# Ascii_of_Main_Board_V1_1.net
KiCad netlist of a schematic drawn in Altium Designer
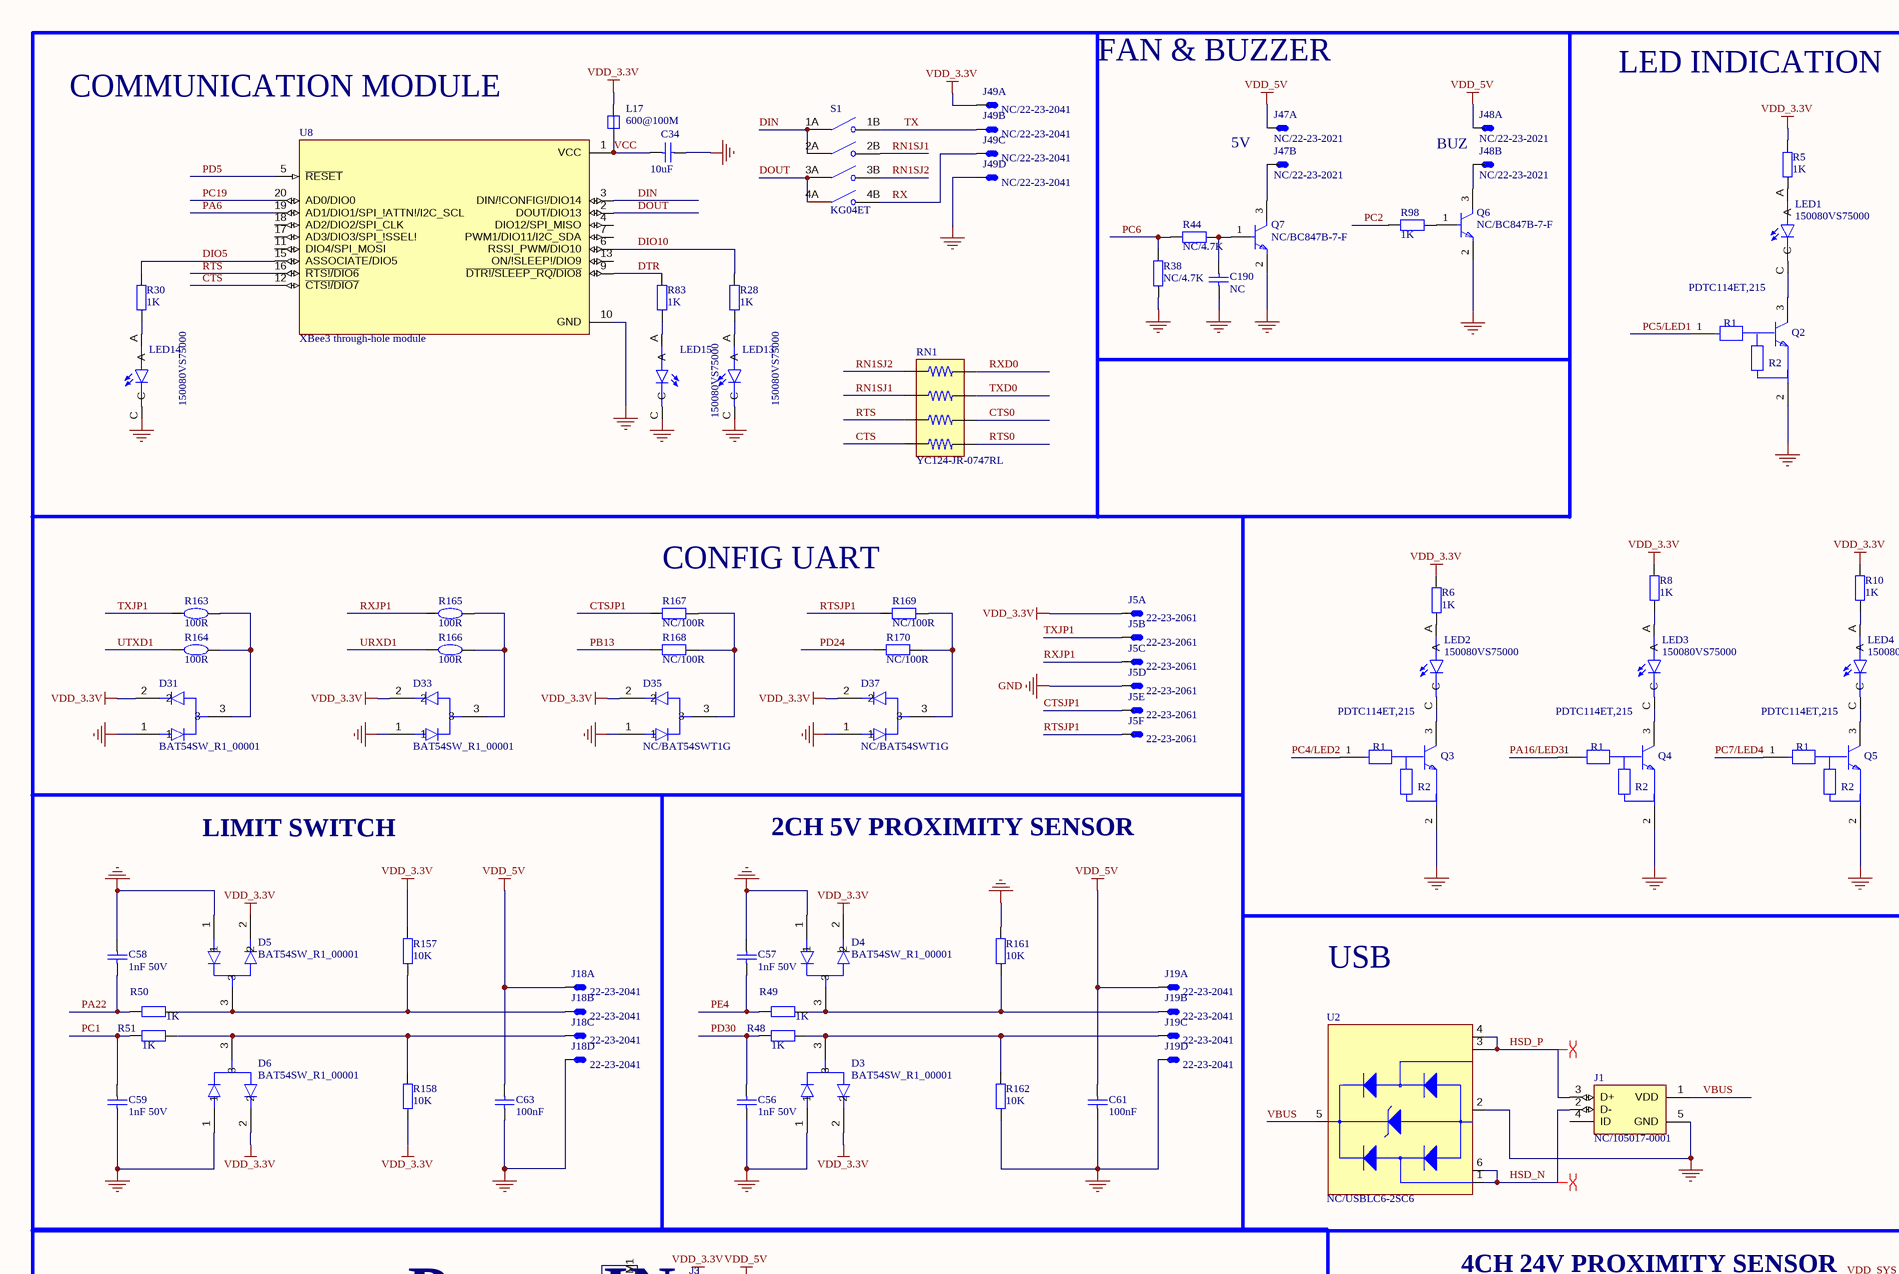
[diagram p0: Ascii of Main Board V1.1.SchDoc, top left]
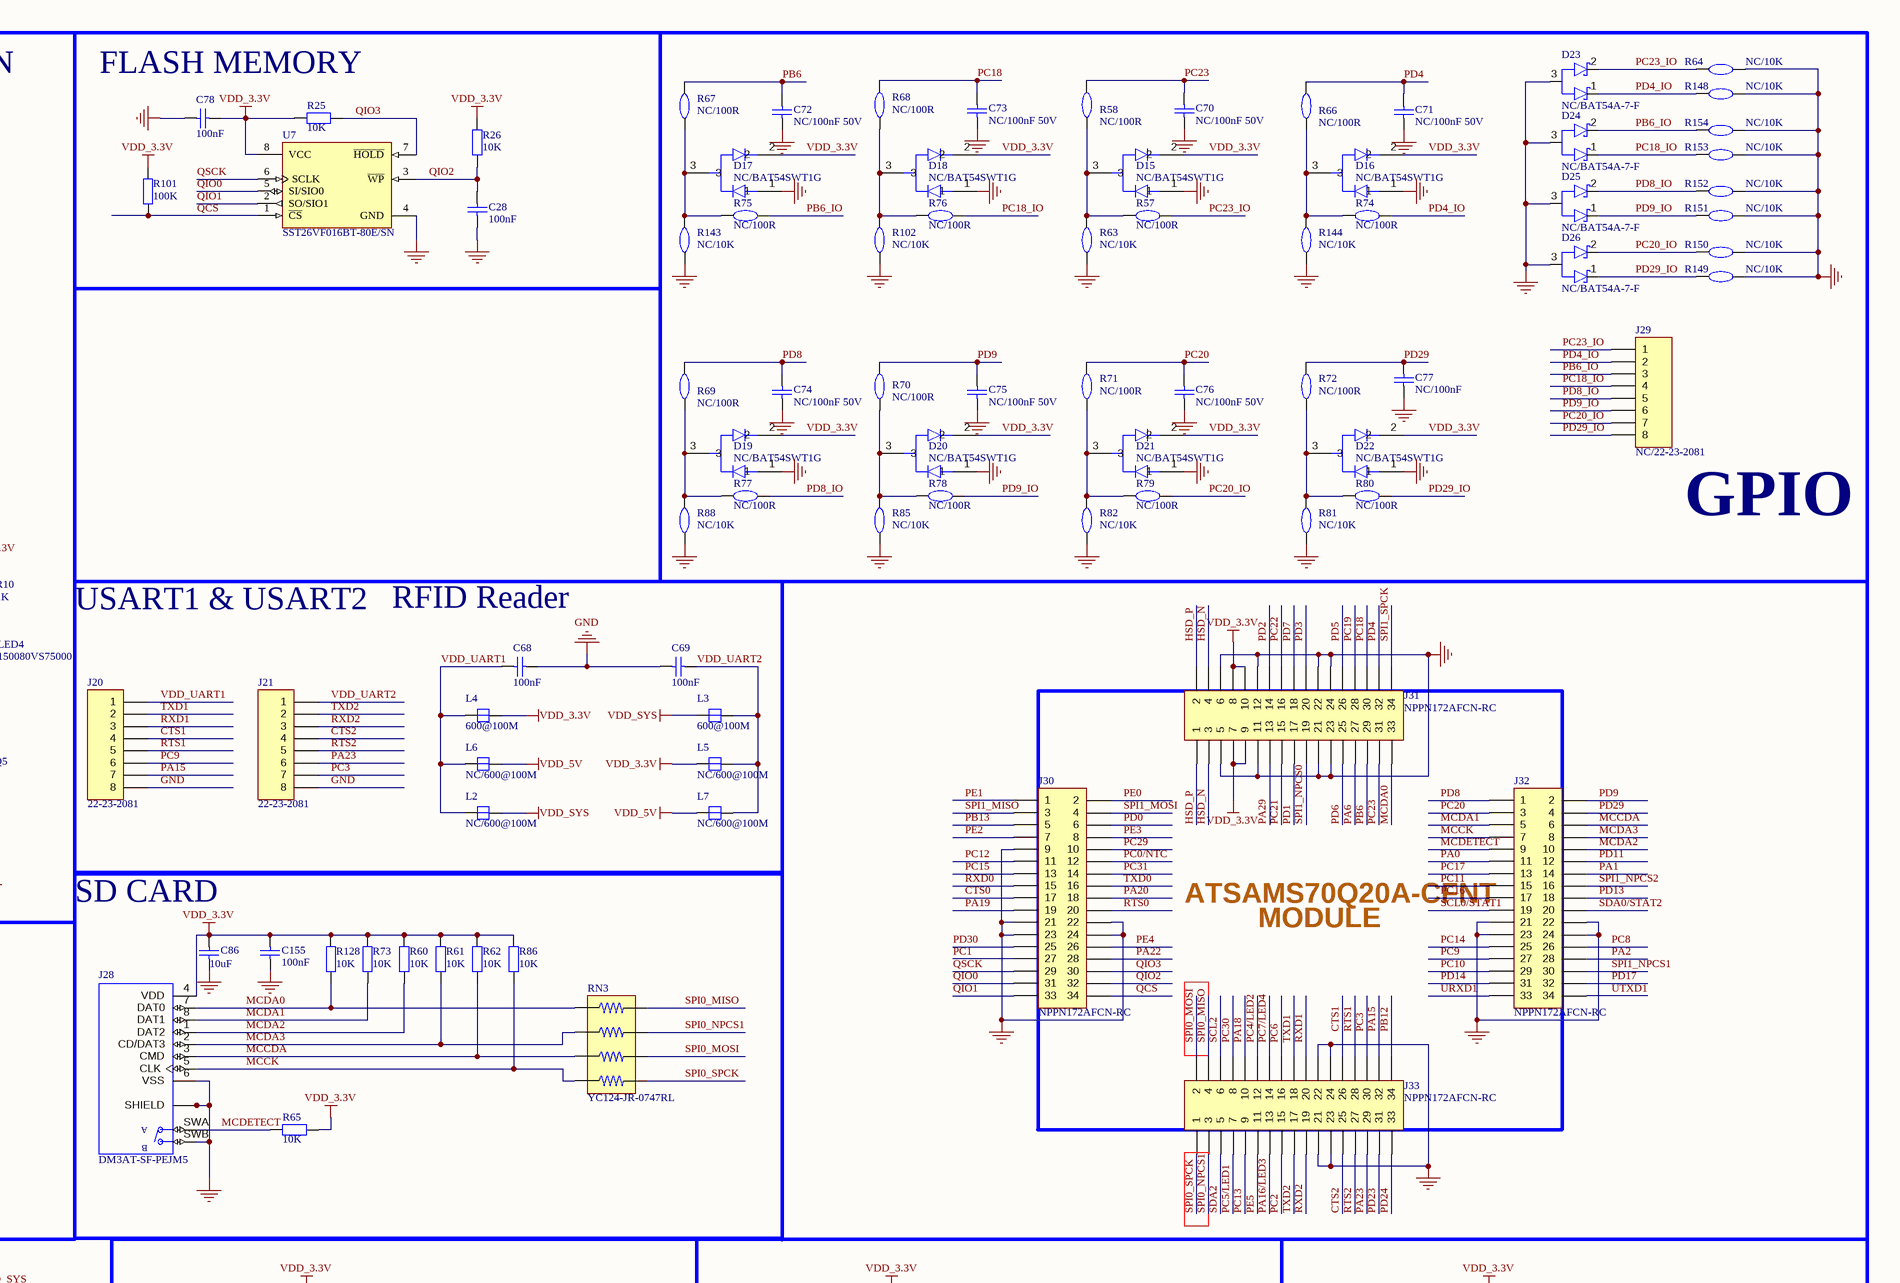
[diagram p1: Ascii of Main Board V1.1.SchDoc, top right]
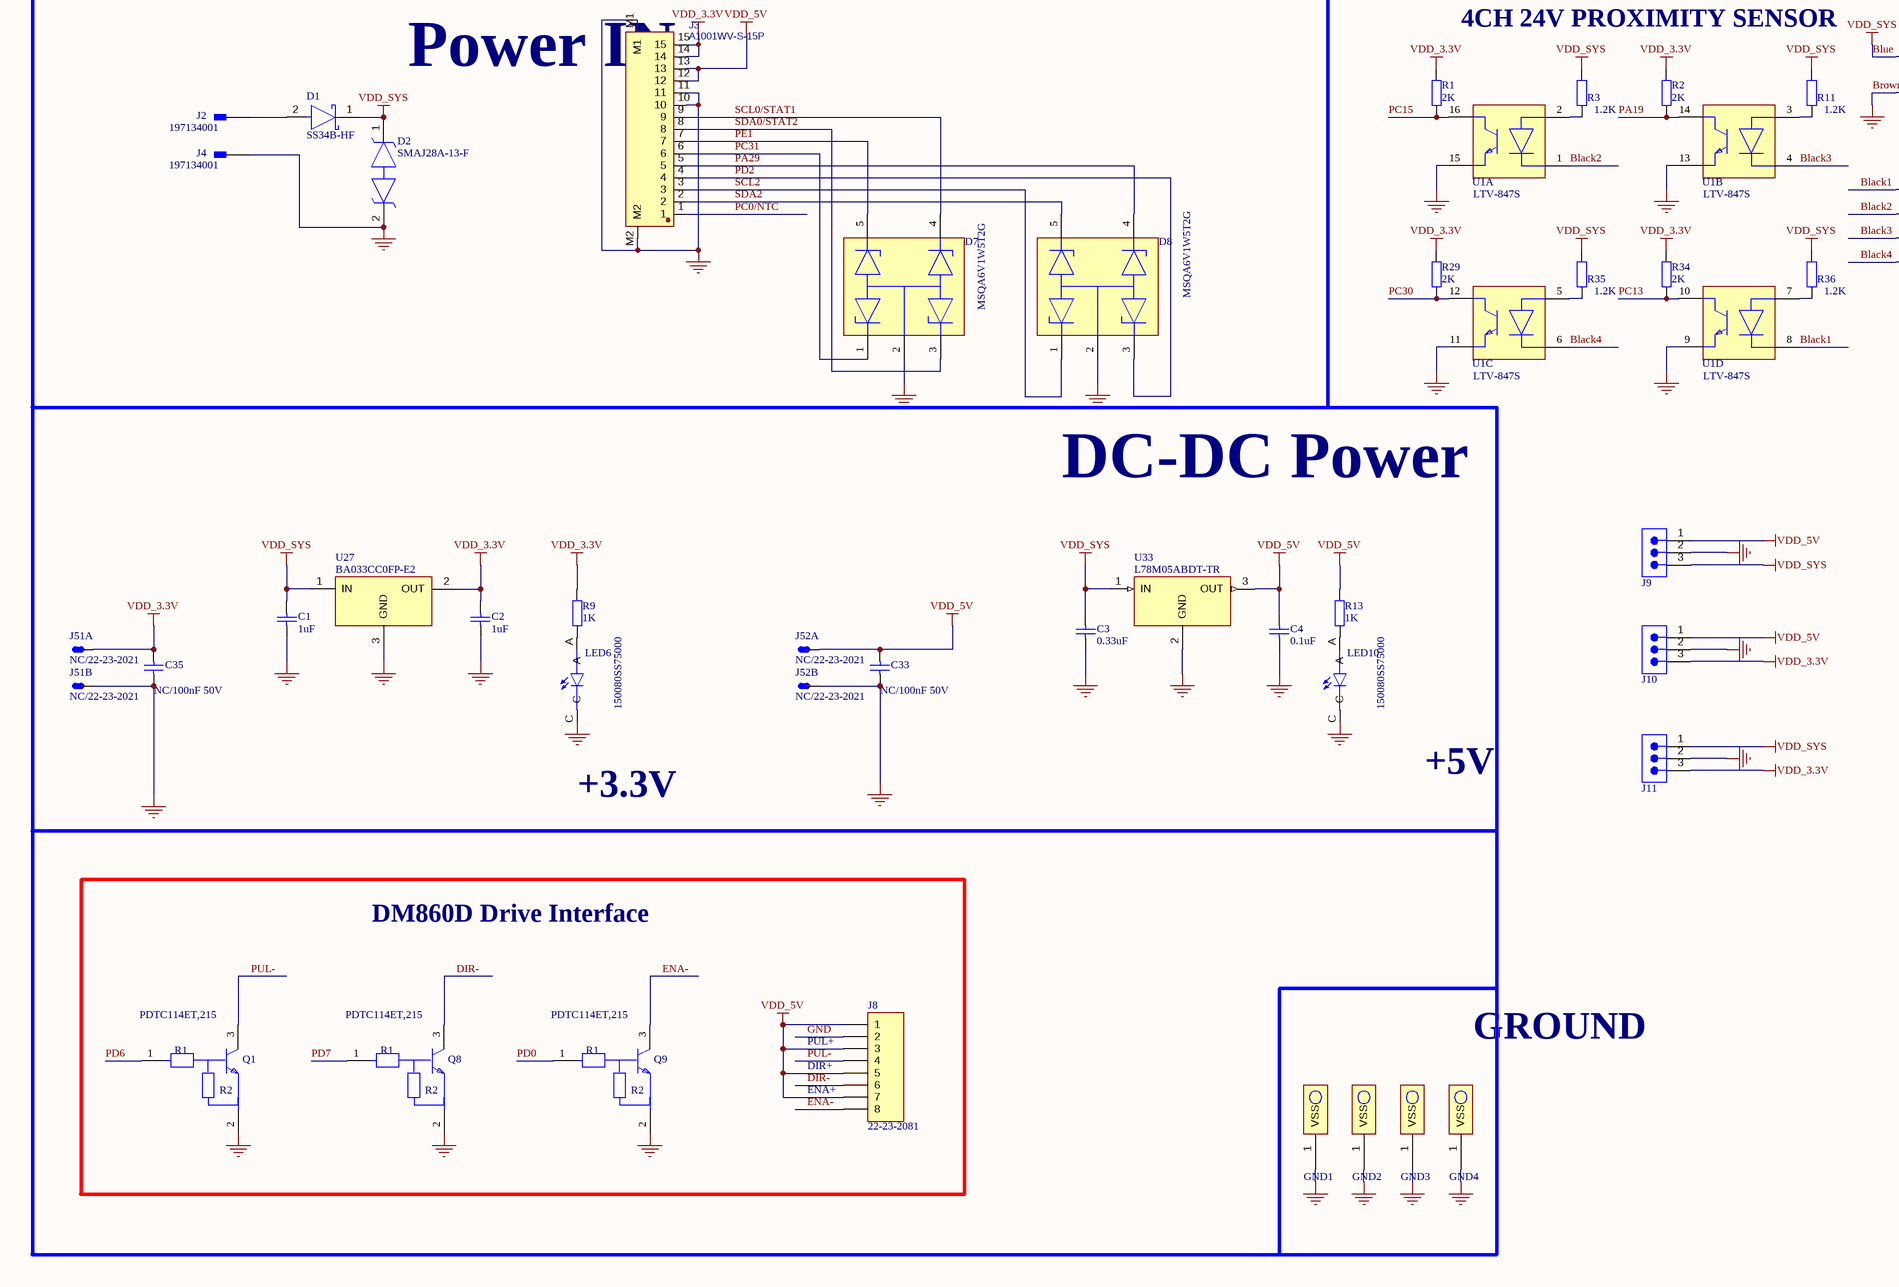
[diagram p2: Ascii of Main Board V1.1.SchDoc, bottom left]
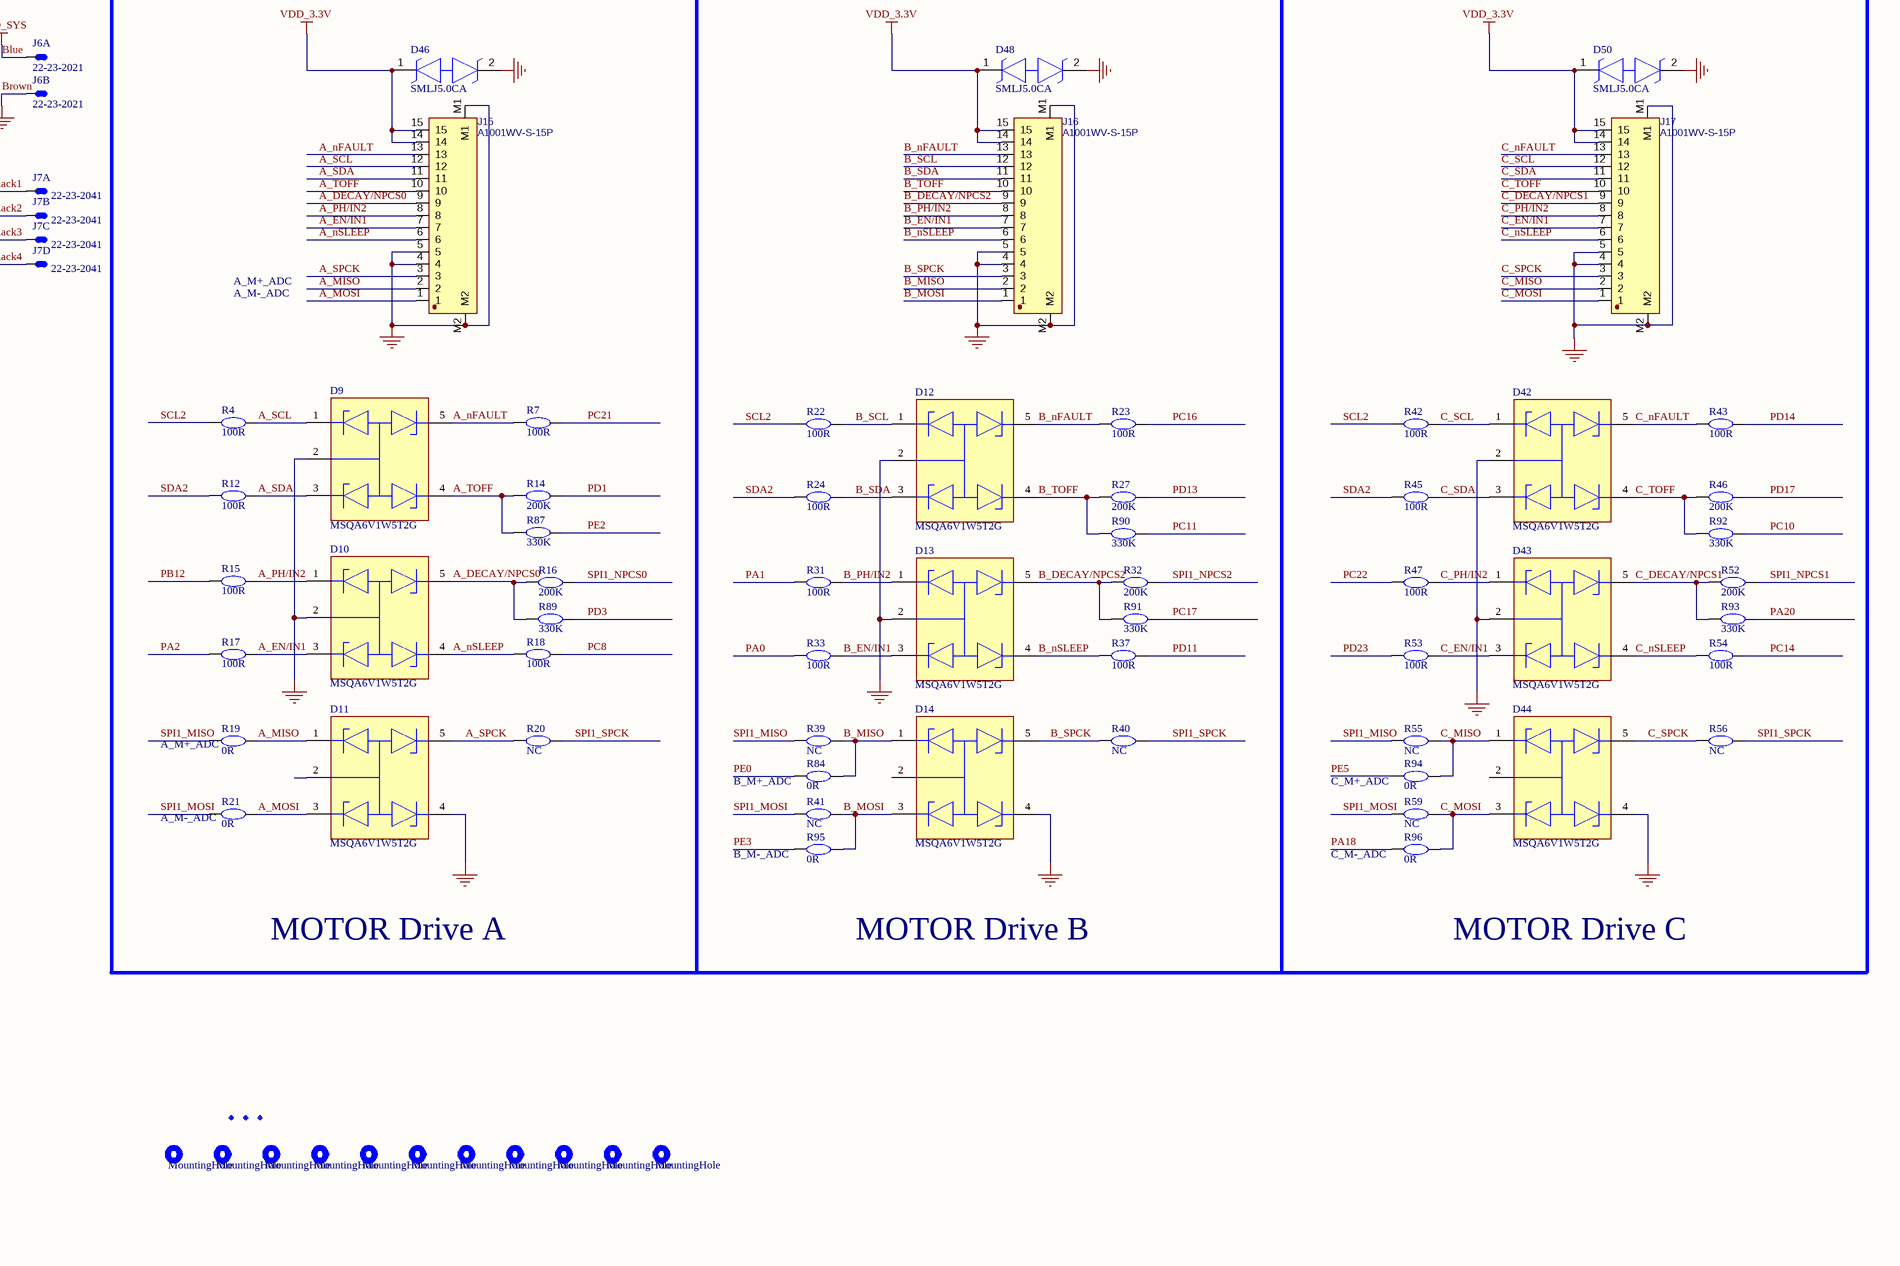
[diagram p3: Ascii of Main Board V1.1.SchDoc, bottom right]

(export (version "E")
  (design (tool "Eeschema 10.0.6"))
  (components
    (comp (ref "C1")
      (value "1uF")
      (footprint "C_0603_1608Metric")
      (description "CAP CER 1UF 50V X7R 0603")
      (fields (field (name "PUBLISHER") "Altium Limited"))
      (libsource (lib "Miscellaneous Devices") (part "Cap Semi"))
    )
    (comp (ref "C2")
      (value "1uF")
      (footprint "C_0603_1608Metric")
      (description "CAP CER 1UF 50V X7R 0603")
      (fields (field (name "PUBLISHER") "Altium Limited"))
      (libsource (lib "Miscellaneous Devices") (part "Cap Semi"))
    )
    (comp (ref "C3")
      (value "0.33uF")
      (footprint "C_0603_1608Metric")
      (description "CAP CER 0.33UF 50V X7R 0603")
      (fields (field (name "PUBLISHER") "Altium Limited"))
      (libsource (lib "Miscellaneous Devices") (part "Cap Semi"))
    )
    (comp (ref "C4")
      (value "0.1uF")
      (footprint "C_0603_1608Metric")
      (description "CAP CER 0.1UF 50V X7R 0603")
      (fields (field (name "PUBLISHER") "Altium Limited"))
      (libsource (lib "Miscellaneous Devices") (part "Cap Semi"))
    )
    (comp (ref "C28")
      (value "100nF")
      (footprint "C_0603_1608Metric")
      (description "CAP CER 0.1UF 50V X7R 0603")
      (fields (field (name "PUBLISHER") "Altium Limited"))
      (libsource (lib "Miscellaneous Devices") (part "Cap Semi"))
    )
    (comp (ref "C33")
      (value "NC/100nF 50V")
      (footprint "C_0603_1608Metric")
      (description "08055C103KAT2A")
      (fields (field (name "PUBLISHER") "Altium Limited"))
      (libsource (lib "Miscellaneous Devices") (part "Cap Semi"))
    )
    (comp (ref "C34")
      (value "10uF")
      (footprint "C_1206_3216Metric")
      (description "CAP CER 10UF 50V X5R 1206")
      (fields (field (name "PUBLISHER") "Altium Limited"))
      (libsource (lib "Miscellaneous Devices") (part "Cap Semi"))
    )
    (comp (ref "C35")
      (value "NC/100nF 50V")
      (footprint "C_0603_1608Metric")
      (description "08055C103KAT2A")
      (fields (field (name "PUBLISHER") "Altium Limited"))
      (libsource (lib "Miscellaneous Devices") (part "Cap Semi"))
    )
    (comp (ref "C56")
      (value "1nF 50V")
      (footprint "C_0603_1608Metric")
      (description "CAP CER 1000PF 50V X7R 0603")
      (fields (field (name "PUBLISHER") "Altium Limited"))
      (libsource (lib "Miscellaneous Devices") (part "Cap Semi"))
    )
    (comp (ref "C57")
      (value "1nF 50V")
      (footprint "C_0603_1608Metric")
      (description "CAP CER 1000PF 50V X7R 0603")
      (fields (field (name "PUBLISHER") "Altium Limited"))
      (libsource (lib "Miscellaneous Devices") (part "Cap Semi"))
    )
    (comp (ref "C58")
      (value "1nF 50V")
      (footprint "C_0603_1608Metric")
      (description "CAP CER 1000PF 50V X7R 0603")
      (fields (field (name "PUBLISHER") "Altium Limited"))
      (libsource (lib "Miscellaneous Devices") (part "Cap Semi"))
    )
    (comp (ref "C59")
      (value "1nF 50V")
      (footprint "C_0603_1608Metric")
      (description "CAP CER 1000PF 50V X7R 0603")
      (fields (field (name "PUBLISHER") "Altium Limited"))
      (libsource (lib "Miscellaneous Devices") (part "Cap Semi"))
    )
    (comp (ref "C61")
      (value "100nF")
      (footprint "C_0603_1608Metric")
      (description "CAP CER 0.1UF 50V X7R 0603")
      (fields (field (name "PUBLISHER") "Altium Limited"))
      (libsource (lib "Miscellaneous Devices") (part "Cap Semi"))
    )
    (comp (ref "C63")
      (value "100nF")
      (footprint "C_0603_1608Metric")
      (description "CAP CER 0.1UF 50V X7R 0603")
      (fields (field (name "PUBLISHER") "Altium Limited"))
      (libsource (lib "Miscellaneous Devices") (part "Cap Semi"))
    )
    (comp (ref "C68")
      (value "100nF")
      (footprint "C_0603_1608Metric")
      (description "CAP CER 0.1UF 50V X7R 0603")
      (fields (field (name "PUBLISHER") "Altium Limited"))
      (libsource (lib "Miscellaneous Devices") (part "Cap Semi"))
    )
    (comp (ref "C69")
      (value "100nF")
      (footprint "C_0603_1608Metric")
      (description "CAP CER 0.1UF 50V X7R 0603")
      (fields (field (name "PUBLISHER") "Altium Limited"))
      (libsource (lib "Miscellaneous Devices") (part "Cap Semi"))
    )
    (comp (ref "C70")
      (value "NC/100nF 50V")
      (footprint "C_0603_1608Metric")
      (description "0805J0500104KXT")
      (fields (field (name "PUBLISHER") "Altium Limited"))
      (libsource (lib "Miscellaneous Devices") (part "Cap Semi"))
    )
    (comp (ref "C71")
      (value "NC/100nF 50V")
      (footprint "C_0603_1608Metric")
      (description "0805J0500104KXT")
      (fields (field (name "PUBLISHER") "Altium Limited"))
      (libsource (lib "Miscellaneous Devices") (part "Cap Semi"))
    )
    (comp (ref "C72")
      (value "NC/100nF 50V")
      (footprint "C_0603_1608Metric")
      (description "0805J0500104KXT")
      (fields (field (name "PUBLISHER") "Altium Limited"))
      (libsource (lib "Miscellaneous Devices") (part "Cap Semi"))
    )
    (comp (ref "C73")
      (value "NC/100nF 50V")
      (footprint "C_0603_1608Metric")
      (description "0805J0500104KXT")
      (fields (field (name "PUBLISHER") "Altium Limited"))
      (libsource (lib "Miscellaneous Devices") (part "Cap Semi"))
    )
    (comp (ref "C74")
      (value "NC/100nF 50V")
      (footprint "C_0603_1608Metric")
      (description "0805J0500104KXT")
      (fields (field (name "PUBLISHER") "Altium Limited"))
      (libsource (lib "Miscellaneous Devices") (part "Cap Semi"))
    )
    (comp (ref "C75")
      (value "NC/100nF 50V")
      (footprint "C_0603_1608Metric")
      (description "0805J0500104KXT")
      (fields (field (name "PUBLISHER") "Altium Limited"))
      (libsource (lib "Miscellaneous Devices") (part "Cap Semi"))
    )
    (comp (ref "C76")
      (value "NC/100nF 50V")
      (footprint "C_0603_1608Metric")
      (description "0805J0500104KXT")
      (fields (field (name "PUBLISHER") "Altium Limited"))
      (libsource (lib "Miscellaneous Devices") (part "Cap Semi"))
    )
    (comp (ref "C77")
      (value "NC/100nF")
      (footprint "C_0603_1608Metric")
      (description "0805J0500104KXT")
      (fields (field (name "PUBLISHER") "Altium Limited"))
      (libsource (lib "Miscellaneous Devices") (part "Cap Semi"))
    )
    (comp (ref "C78")
      (value "100nF")
      (footprint "C_0603_1608Metric")
      (description "CAP CER 0.1UF 50V X7R 0603")
      (fields (field (name "PUBLISHER") "Altium Limited"))
      (libsource (lib "Miscellaneous Devices") (part "Cap Semi"))
    )
    (comp (ref "C86")
      (value "10uF")
      (footprint "C_1206_3216Metric")
      (description "CAP CER 10UF 50V X5R 1206")
      (fields (field (name "PUBLISHER") "Altium Limited"))
      (libsource (lib "Miscellaneous Devices") (part "Cap Semi"))
    )
    (comp (ref "C155")
      (value "100nF")
      (footprint "C_0603_1608Metric")
      (description "CAP CER 0.1UF 50V X7R 0603")
      (fields (field (name "PUBLISHER") "Altium Limited"))
      (libsource (lib "Miscellaneous Devices") (part "Cap Semi"))
    )
    (comp (ref "C190")
      (value "NC")
      (footprint "C_0603_1608Metric")
      (description "DUMMY")
      (fields (field (name "PUBLISHER") "Altium Limited"))
      (libsource (lib "Miscellaneous Devices") (part "Cap Semi"))
    )
    (comp (ref "D1")
      (value "SS34B-HF")
      (footprint "FP-95402-MFG")
      (description "DIODE SCHOTTKY 40V 3A DO214AB")
      (libsource (lib "Main Board V1.1") (part "1d6ec82d83fb6aee721767c19dac4b9"))
    )
    (comp (ref "D2")
      (value "SMAJ28A-13-F")
      (footprint "DIONM7959X262N")
      (description "TVS Diode (Bi-directional)")
      (fields
        (field (name "MANUFACTURER_PART_NUMBER") "SMLJ43CA")
        (field (name "MOUSER PART NUMBER") "652-SMLJ43CA")
      )
      (libsource (lib "SamacSys") (part "SMLJ43CA"))
    )
    (comp (ref "D3")
      (value "BAT54SW_R1_00001")
      (footprint "ONSC-SOT-323-3-419-04_V")
      (description "Diode Array 1 Pair Series Connection Schottky 30V 200mA Surface Mount TO-236-3, SC-59, SOT-23-3")
      (fields (field (name "MF") "ON Semiconductor") (field (name "MP") "BAT54S"))
      (libsource (lib "SamacSys") (part "BAT54S"))
    )
    (comp (ref "D4")
      (value "BAT54SW_R1_00001")
      (footprint "ONSC-SOT-323-3-419-04_V")
      (description "Diode Array 1 Pair Series Connection Schottky 30V 200mA Surface Mount TO-236-3, SC-59, SOT-23-3")
      (fields (field (name "MF") "ON Semiconductor") (field (name "MP") "BAT54S"))
      (libsource (lib "SamacSys") (part "BAT54S"))
    )
    (comp (ref "D5")
      (value "BAT54SW_R1_00001")
      (footprint "ONSC-SOT-323-3-419-04_V")
      (description "Diode Array 1 Pair Series Connection Schottky 30V 200mA Surface Mount TO-236-3, SC-59, SOT-23-3")
      (fields (field (name "MF") "ON Semiconductor") (field (name "MP") "BAT54S"))
      (libsource (lib "SamacSys") (part "BAT54S"))
    )
    (comp (ref "D6")
      (value "BAT54SW_R1_00001")
      (footprint "ONSC-SOT-323-3-419-04_V")
      (description "Diode Array 1 Pair Series Connection Schottky 30V 200mA Surface Mount TO-236-3, SC-59, SOT-23-3")
      (fields (field (name "MF") "ON Semiconductor") (field (name "MP") "BAT54S"))
      (libsource (lib "SamacSys") (part "BAT54S"))
    )
    (comp (ref "D7")
      (value "MSQA6V1W5T2G")
      (footprint "SOT95P280X145-5N")
      (description "Low capacitance unidirectional quadruple ESD protection diode arrays")
      (libsource (lib "SamacSys") (part "PESD3V3L4UW"))
    )
    (comp (ref "D8")
      (value "MSQA6V1W5T2G")
      (footprint "SOT95P280X145-5N")
      (description "Low capacitance unidirectional quadruple ESD protection diode arrays")
      (libsource (lib "SamacSys") (part "PESD3V3L4UW"))
    )
    (comp (ref "D9")
      (value "MSQA6V1W5T2G")
      (footprint "SOT95P280X145-5N")
      (description "Low capacitance unidirectional quadruple ESD protection diode arrays")
      (libsource (lib "") (part "PESD3V3L4UW_1"))
    )
    (comp (ref "D10")
      (value "MSQA6V1W5T2G")
      (footprint "SOT95P280X145-5N")
      (description "Low capacitance unidirectional quadruple ESD protection diode arrays")
      (libsource (lib "") (part "PESD3V3L4UW_1"))
    )
    (comp (ref "D11")
      (value "MSQA6V1W5T2G")
      (footprint "SOT95P280X145-5N")
      (description "Low capacitance unidirectional quadruple ESD protection diode arrays")
      (libsource (lib "") (part "PESD3V3L4UW_1"))
    )
    (comp (ref "D12")
      (value "MSQA6V1W5T2G")
      (footprint "SOT95P280X145-5N")
      (description "Low capacitance unidirectional quadruple ESD protection diode arrays")
      (libsource (lib "") (part "PESD3V3L4UW_1"))
    )
    (comp (ref "D13")
      (value "MSQA6V1W5T2G")
      (footprint "SOT95P280X145-5N")
      (description "Low capacitance unidirectional quadruple ESD protection diode arrays")
      (libsource (lib "") (part "PESD3V3L4UW_1"))
    )
    (comp (ref "D14")
      (value "MSQA6V1W5T2G")
      (footprint "SOT95P280X145-5N")
      (description "Low capacitance unidirectional quadruple ESD protection diode arrays")
      (libsource (lib "") (part "PESD3V3L4UW_1"))
    )
    (comp (ref "D15")
      (value "NC/BAT54SWT1G")
      (footprint "ONSC-SOT-323-3-419-04_V")
      (description "Diode Array 1 Pair Series Connection Schottky 30V 200mA Surface Mount TO-236-3, SC-59, SOT-23-3")
      (fields (field (name "MF") "ON Semiconductor") (field (name "MP") "BAT54S"))
      (libsource (lib "BAT54S") (part "BAT54S"))
    )
    (comp (ref "D16")
      (value "NC/BAT54SWT1G")
      (footprint "ONSC-SOT-323-3-419-04_V")
      (description "Diode Array 1 Pair Series Connection Schottky 30V 200mA Surface Mount TO-236-3, SC-59, SOT-23-3")
      (fields (field (name "MF") "ON Semiconductor") (field (name "MP") "BAT54S"))
      (libsource (lib "BAT54S") (part "BAT54S"))
    )
    (comp (ref "D17")
      (value "NC/BAT54SWT1G")
      (footprint "ONSC-SOT-323-3-419-04_V")
      (description "Diode Array 1 Pair Series Connection Schottky 30V 200mA Surface Mount TO-236-3, SC-59, SOT-23-3")
      (fields (field (name "MF") "ON Semiconductor") (field (name "MP") "BAT54S"))
      (libsource (lib "BAT54S") (part "BAT54S"))
    )
    (comp (ref "D18")
      (value "NC/BAT54SWT1G")
      (footprint "ONSC-SOT-323-3-419-04_V")
      (description "Diode Array 1 Pair Series Connection Schottky 30V 200mA Surface Mount TO-236-3, SC-59, SOT-23-3")
      (fields (field (name "MF") "ON Semiconductor") (field (name "MP") "BAT54S"))
      (libsource (lib "BAT54S") (part "BAT54S"))
    )
    (comp (ref "D19")
      (value "NC/BAT54SWT1G")
      (footprint "ONSC-SOT-323-3-419-04_V")
      (description "Diode Array 1 Pair Series Connection Schottky 30V 200mA Surface Mount TO-236-3, SC-59, SOT-23-3")
      (fields (field (name "MF") "ON Semiconductor") (field (name "MP") "BAT54S"))
      (libsource (lib "BAT54S") (part "BAT54S"))
    )
    (comp (ref "D20")
      (value "NC/BAT54SWT1G")
      (footprint "ONSC-SOT-323-3-419-04_V")
      (description "Diode Array 1 Pair Series Connection Schottky 30V 200mA Surface Mount TO-236-3, SC-59, SOT-23-3")
      (fields (field (name "MF") "ON Semiconductor") (field (name "MP") "BAT54S"))
      (libsource (lib "BAT54S") (part "BAT54S"))
    )
    (comp (ref "D21")
      (value "NC/BAT54SWT1G")
      (footprint "ONSC-SOT-323-3-419-04_V")
      (description "Diode Array 1 Pair Series Connection Schottky 30V 200mA Surface Mount TO-236-3, SC-59, SOT-23-3")
      (fields (field (name "MF") "ON Semiconductor") (field (name "MP") "BAT54S"))
      (libsource (lib "BAT54S") (part "BAT54S"))
    )
    (comp (ref "D22")
      (value "NC/BAT54SWT1G")
      (footprint "ONSC-SOT-323-3-419-04_V")
      (description "Diode Array 1 Pair Series Connection Schottky 30V 200mA Surface Mount TO-236-3, SC-59, SOT-23-3")
      (fields (field (name "MF") "ON Semiconductor") (field (name "MP") "BAT54S"))
      (libsource (lib "BAT54S") (part "BAT54S"))
    )
    (comp (ref "D23")
      (value "NC/BAT54A-7-F")
      (footprint "ONSC-SOT-323-3-419-04_V")
      (description "Diode Array 1 Pair Common Anode Schottky 30V 200mA (DC) Surface Mount TO-236-3, SC-59, SOT-23-3")
      (fields (field (name "MP") "BAT54A-7-F") (field (name "MF") "Diodes Inc."))
      (libsource (lib "SamacSys") (part "BAT54A-7-F"))
    )
    (comp (ref "D24")
      (value "NC/BAT54A-7-F")
      (footprint "ONSC-SOT-323-3-419-04_V")
      (description "Diode Array 1 Pair Common Anode Schottky 30V 200mA (DC) Surface Mount TO-236-3, SC-59, SOT-23-3")
      (fields (field (name "MP") "BAT54A-7-F") (field (name "MF") "Diodes Inc."))
      (libsource (lib "SamacSys") (part "BAT54A-7-F"))
    )
    (comp (ref "D25")
      (value "NC/BAT54A-7-F")
      (footprint "ONSC-SOT-323-3-419-04_V")
      (description "Diode Array 1 Pair Common Anode Schottky 30V 200mA (DC) Surface Mount TO-236-3, SC-59, SOT-23-3")
      (fields (field (name "MP") "BAT54A-7-F") (field (name "MF") "Diodes Inc."))
      (libsource (lib "SamacSys") (part "BAT54A-7-F"))
    )
    (comp (ref "D26")
      (value "NC/BAT54A-7-F")
      (footprint "ONSC-SOT-323-3-419-04_V")
      (description "Diode Array 1 Pair Common Anode Schottky 30V 200mA (DC) Surface Mount TO-236-3, SC-59, SOT-23-3")
      (fields (field (name "MP") "BAT54A-7-F") (field (name "MF") "Diodes Inc."))
      (libsource (lib "SamacSys") (part "BAT54A-7-F"))
    )
    (comp (ref "D31")
      (value "BAT54SW_R1_00001")
      (footprint "ONSC-SOT-323-3-419-04_V")
      (description "Diode Array 1 Pair Series Connection Schottky 30V 200mA Surface Mount TO-236-3, SC-59, SOT-23-3")
      (fields (field (name "MF") "ON Semiconductor") (field (name "MP") "BAT54S"))
      (libsource (lib "SamacSys") (part "BAT54S"))
    )
    (comp (ref "D33")
      (value "BAT54SW_R1_00001")
      (footprint "ONSC-SOT-323-3-419-04_V")
      (description "Diode Array 1 Pair Series Connection Schottky 30V 200mA Surface Mount TO-236-3, SC-59, SOT-23-3")
      (fields (field (name "MF") "ON Semiconductor") (field (name "MP") "BAT54S"))
      (libsource (lib "SamacSys") (part "BAT54S"))
    )
    (comp (ref "D35")
      (value "NC/BAT54SWT1G")
      (footprint "ONSC-SOT-323-3-419-04_V")
      (fields
        (field (name "DIGI-KEY_PART_NUMBER") "BAT54SCT-ND")
        (field (name "MP") "BAT54STA")
        (field (name "MF") "Diodes Inc.")
      )
      (libsource (lib "Zigbee Sch Lib_SJCH") (part "BAT54STA"))
    )
    (comp (ref "D37")
      (value "NC/BAT54SWT1G")
      (footprint "ONSC-SOT-323-3-419-04_V")
      (fields
        (field (name "DIGI-KEY_PART_NUMBER") "BAT54SCT-ND")
        (field (name "MP") "BAT54STA")
        (field (name "MF") "Diodes Inc.")
      )
      (libsource (lib "Zigbee Sch Lib_SJCH") (part "BAT54STA"))
    )
    (comp (ref "D42")
      (value "MSQA6V1W5T2G")
      (footprint "SOT95P280X145-5N")
      (description "Low capacitance unidirectional quadruple ESD protection diode arrays")
      (libsource (lib "") (part "PESD3V3L4UW_1"))
    )
    (comp (ref "D43")
      (value "MSQA6V1W5T2G")
      (footprint "SOT95P280X145-5N")
      (description "Low capacitance unidirectional quadruple ESD protection diode arrays")
      (libsource (lib "") (part "PESD3V3L4UW_1"))
    )
    (comp (ref "D44")
      (value "MSQA6V1W5T2G")
      (footprint "SOT95P280X145-5N")
      (description "Low capacitance unidirectional quadruple ESD protection diode arrays")
      (libsource (lib "") (part "PESD3V3L4UW_1"))
    )
    (comp (ref "D46")
      (value "SMLJ5.0CA")
      (footprint "DIONM7959X262N")
      (description "TVS Diode (Bi-directional)")
      (fields
        (field (name "MANUFACTURER_PART_NUMBER") "SMLJ43CA")
        (field (name "MOUSER PART NUMBER") "652-SMLJ43CA")
      )
      (libsource (lib "SamacSys") (part "SMLJ43CA"))
    )
    (comp (ref "D48")
      (value "SMLJ5.0CA")
      (footprint "DIONM7959X262N")
      (description "TVS Diode (Bi-directional)")
      (fields
        (field (name "MANUFACTURER_PART_NUMBER") "SMLJ43CA")
        (field (name "MOUSER PART NUMBER") "652-SMLJ43CA")
      )
      (libsource (lib "SamacSys") (part "SMLJ43CA"))
    )
    (comp (ref "D50")
      (value "SMLJ5.0CA")
      (footprint "DIONM7959X262N")
      (description "TVS Diode (Bi-directional)")
      (fields
        (field (name "MANUFACTURER_PART_NUMBER") "SMLJ43CA")
        (field (name "MOUSER PART NUMBER") "652-SMLJ43CA")
      )
      (libsource (lib "SamacSys") (part "SMLJ43CA"))
    )
    (comp (ref "Fid1")
      (value "Fiducial mark")
      (footprint "Fiducial_1mm_Mask2mm")
      (description "Fiducial Mark")
      (fields (field (name "PART NUMBER") "Fid-Mark") (field (name "PUBLISHER") "Nordic Semiconductor"))
      (libsource (lib "Altium lib") (part "Fiducial"))
    )
    (comp (ref "Fid2")
      (value "Fiducial mark")
      (footprint "Fiducial_1mm_Mask2mm")
      (description "Fiducial Mark")
      (fields (field (name "PART NUMBER") "Fid-Mark") (field (name "PUBLISHER") "Nordic Semiconductor"))
      (libsource (lib "Altium lib") (part "Fiducial"))
    )
    (comp (ref "Fid3")
      (value "Fiducial mark")
      (footprint "Fiducial_1mm_Mask2mm")
      (description "Fiducial Mark")
      (fields (field (name "PART NUMBER") "Fid-Mark") (field (name "PUBLISHER") "Nordic Semiconductor"))
      (libsource (lib "Altium lib") (part "Fiducial"))
    )
    (comp (ref "GND1")
      (value "Ground Mark")
      (footprint "1X01")
      (libsource (lib "Zigbee Sch Lib_SJCH") (part "Ground Mark"))
    )
    (comp (ref "GND2")
      (value "Ground Mark")
      (footprint "1X01")
      (libsource (lib "Zigbee Sch Lib_SJCH") (part "Ground Mark"))
    )
    (comp (ref "GND3")
      (value "Ground Mark")
      (footprint "1X01")
      (libsource (lib "Zigbee Sch Lib_SJCH") (part "Ground Mark"))
    )
    (comp (ref "GND4")
      (value "Ground Mark")
      (footprint "1X01")
      (libsource (lib "Zigbee Sch Lib_SJCH") (part "Ground Mark"))
    )
    (comp (ref "H1")
      (value "MountingHole")
      (footprint "3,0-PAD")
      (libsource (lib "SamacSys") (part "MountingHole"))
    )
    (comp (ref "H2")
      (value "MountingHole")
      (footprint "3,0-PAD")
      (libsource (lib "SamacSys") (part "MountingHole"))
    )
    (comp (ref "H3")
      (value "MountingHole")
      (footprint "3,0-PAD")
      (libsource (lib "SamacSys") (part "MountingHole"))
    )
    (comp (ref "H4")
      (value "MountingHole")
      (footprint "3,0-PAD")
      (libsource (lib "SamacSys") (part "MountingHole"))
    )
    (comp (ref "H5")
      (value "MountingHole")
      (footprint "3,0-PAD")
      (libsource (lib "SamacSys") (part "MountingHole"))
    )
    (comp (ref "H6")
      (value "MountingHole")
      (footprint "3,0-PAD")
      (libsource (lib "SamacSys") (part "MountingHole"))
    )
    (comp (ref "H7")
      (value "MountingHole")
      (footprint "3,0-PAD")
      (libsource (lib "SamacSys") (part "MountingHole"))
    )
    (comp (ref "H8")
      (value "MountingHole")
      (footprint "3,0-PAD")
      (libsource (lib "SamacSys") (part "MountingHole"))
    )
    (comp (ref "H9")
      (value "MountingHole")
      (footprint "3,0-PAD")
      (libsource (lib "SamacSys") (part "MountingHole"))
    )
    (comp (ref "H10")
      (value "MountingHole")
      (footprint "3,0-PAD")
      (libsource (lib "SamacSys") (part "MountingHole"))
    )
    (comp (ref "H11")
      (value "MountingHole")
      (footprint "3,0-PAD")
      (libsource (lib "SamacSys") (part "MountingHole"))
    )
    (comp (ref "J1")
      (value "NC/105017-0001")
      (footprint "MOLEX_105017-0001")
      (fields (field (name "MP") "105017-0001") (field (name "MF") "Molex"))
      (libsource (lib "SnapEDAsch") (part "105017-0001"))
    )
    (comp (ref "J2")
      (value "197134001")
      (footprint "Crimp male 90 degree 0.25(6.35mm)")
      (description "Flachstecker Typ tyco/Electronics/AMP   Printed Circuit Board Tabs Source: http://www.buerklin.com")
      (fields (field (name "MF") "MF") (field (name "MPN") "MPN") (field (name "LIBRARYNAME") "con-faston"))
      (libsource (lib "SamacSys") (part "PIN3F061.120"))
    )
    (comp (ref "J3")
      (value "A1001WV-S-15P")
      (footprint "SH1.0 1X15P SMT VERTICAL")
      (fields
        (field (name "BOM_SUPPLIER PART") "C519176")
        (field (name "BOM_MANUFACTURER PART") "X2016WRS-10-9TSW")
        (field (name "CONTRIBUTOR") "LCSC")
      )
      (libsource (lib "") (part "1x15P SMT Connector_1"))
    )
    (comp (ref "J4")
      (value "197134001")
      (footprint "Crimp male 90 degree 0.25(6.35mm)")
      (description "Flachstecker Typ tyco/Electronics/AMP   Printed Circuit Board Tabs Source: http://www.buerklin.com")
      (fields (field (name "MF") "MF") (field (name "MPN") "MPN") (field (name "LIBRARYNAME") "con-faston"))
      (libsource (lib "SamacSys") (part "PIN3F061.120"))
    )
    (comp (ref "J5")
      (value "22-23-2061")
      (footprint "22-23-2061:22-23-2061")
      (description "Connector Header Through Hole 6 position 0.100 (2.54mm)")
      (fields (field (name "MF") "Molex"))
      (libsource (lib "SamacSys") (part "22-23-2061"))
    )
    (comp (ref "J6")
      (value "22-23-2021")
      (footprint "22-23-2021")
      (description "Connector Header Through Hole 2 position 0.100 (2.54mm)")
      (fields (field (name "MP") "22232021") (field (name "MF") "Molex"))
      (libsource (lib "SamacSys") (part "22-23-2021"))
    )
    (comp (ref "J7")
      (value "22-23-2041")
      (footprint "22-23-2041")
      (description "Connector Header Through Hole 4 position 0.100 (2.54mm)")
      (fields (field (name "MF") "Molex"))
      (libsource (lib "SamacSys") (part "22-23-2041"))
    )
    (comp (ref "J8")
      (value "22-23-2081")
      (footprint "22-23-2081")
      (description "Header, 8-Pin")
      (fields (field (name "PUBLISHER") "Altium Limited"))
      (libsource (lib "Miscellaneous Connectors") (part "Header 8"))
    )
    (comp (ref "J9")
      (value "61300311121")
      (footprint "61300311121")
      (description "WR-PHD Pin Header, THT, Vertical, pitch 2.54mm, 1 Row, 3P")
      (fields (field (name "MANUFACTURER") "Wurth Elektronik"))
      (libsource (lib "Main Board V1.1") (part "61300311121"))
    )
    (comp (ref "J10")
      (value "61300311121")
      (footprint "61300311121")
      (description "WR-PHD Pin Header, THT, Vertical, pitch 2.54mm, 1 Row, 3P")
      (fields (field (name "MANUFACTURER") "Wurth Elektronik"))
      (libsource (lib "Main Board V1.1") (part "61300311121"))
    )
    (comp (ref "J11")
      (value "61300311121")
      (footprint "61300311121")
      (description "WR-PHD Pin Header, THT, Vertical, pitch 2.54mm, 1 Row, 3P")
      (fields (field (name "MANUFACTURER") "Wurth Elektronik"))
      (libsource (lib "Main Board V1.1") (part "61300311121"))
    )
    (comp (ref "J15")
      (value "A1001WV-S-15P")
      (footprint "SH1.0 1X15P SMT VERTICAL")
      (fields
        (field (name "BOM_SUPPLIER PART") "C519176")
        (field (name "BOM_MANUFACTURER PART") "X2016WRS-10-9TSW")
        (field (name "CONTRIBUTOR") "LCSC")
      )
      (libsource (lib "Altium lib") (part "1x15P SMT Connector"))
    )
    (comp (ref "J16")
      (value "A1001WV-S-15P")
      (footprint "SH1.0 1X15P SMT VERTICAL")
      (fields
        (field (name "BOM_SUPPLIER PART") "C519176")
        (field (name "BOM_MANUFACTURER PART") "X2016WRS-10-9TSW")
        (field (name "CONTRIBUTOR") "LCSC")
      )
      (libsource (lib "Altium lib") (part "1x15P SMT Connector"))
    )
    (comp (ref "J17")
      (value "A1001WV-S-15P")
      (footprint "SH1.0 1X15P SMT VERTICAL")
      (fields
        (field (name "BOM_SUPPLIER PART") "C519176")
        (field (name "BOM_MANUFACTURER PART") "X2016WRS-10-9TSW")
        (field (name "CONTRIBUTOR") "LCSC")
      )
      (libsource (lib "Altium lib") (part "1x15P SMT Connector"))
    )
    (comp (ref "J18")
      (value "22-23-2041")
      (footprint "22-23-2041:22-23-2041")
      (description "Connector Header Through Hole 4 position 0.100 (2.54mm)")
      (fields (field (name "MF") "Molex"))
      (libsource (lib "SamacSys") (part "22-23-2041"))
    )
    (comp (ref "J19")
      (value "22-23-2041")
      (footprint "22-23-2041:22-23-2041")
      (description "Connector Header Through Hole 4 position 0.100 (2.54mm)")
      (fields (field (name "MF") "Molex"))
      (libsource (lib "SamacSys") (part "22-23-2041"))
    )
    (comp (ref "J20")
      (value "22-23-2081")
      (footprint "22-23-2081")
      (description "Header, 8-Pin")
      (fields (field (name "PUBLISHER") "Altium Limited"))
      (libsource (lib "") (part "Header 8_1"))
    )
    (comp (ref "J21")
      (value "22-23-2081")
      (footprint "22-23-2081")
      (description "Header, 8-Pin")
      (fields (field (name "PUBLISHER") "Altium Limited"))
      (libsource (lib "") (part "Header 8_1"))
    )
    (comp (ref "J28")
      (value "DM3AT-SF-PEJM5")
      (footprint "HRS_DM3AT-SF-PEJM5")
      (description "CONN MICRO SD CARD PUSH-PUSH R/A")
      (fields (field (name "MF") "Hirose"))
      (libsource (lib "Zigbee Sch Lib_SJCH") (part "DM3AT-SF-PEJM5"))
    )
    (comp (ref "J29")
      (value "NC/22-23-2081")
      (footprint "22-23-2081")
      (description "Header, 8-Pin")
      (fields (field (name "PUBLISHER") "Altium Limited"))
      (libsource (lib "Miscellaneous Connectors") (part "Header 8"))
    )
    (comp (ref "J30")
      (value "NPPN172AFCN-RC")
      (footprint "HDR-TH_34P-P2.00-V-M-R2-C17-S2.00")
      (description "Header, 17-Pin, Dual row")
      (fields (field (name "PUBLISHER") "Altium Limited"))
      (libsource (lib "") (part "Header 17X2_1"))
    )
    (comp (ref "J31")
      (value "NPPN172AFCN-RC")
      (footprint "HDR-TH_34P-P2.00-V-M-R2-C17-S2.00")
      (description "Header, 17-Pin, Dual row")
      (fields (field (name "PUBLISHER") "Altium Limited"))
      (libsource (lib "Miscellaneous Connectors") (part "Header 17X2"))
    )
    (comp (ref "J32")
      (value "NPPN172AFCN-RC")
      (footprint "HDR-TH_34P-P2.00-V-M-R2-C17-S2.00")
      (description "Header, 17-Pin, Dual row")
      (fields (field (name "PUBLISHER") "Altium Limited"))
      (libsource (lib "") (part "Header 17X2_1"))
    )
    (comp (ref "J33")
      (value "NPPN172AFCN-RC")
      (footprint "HDR-TH_34P-P2.00-V-M-R2-C17-S2.00")
      (description "Header, 17-Pin, Dual row")
      (fields (field (name "PUBLISHER") "Altium Limited"))
      (libsource (lib "Miscellaneous Connectors") (part "Header 17X2"))
    )
    (comp (ref "J47")
      (value "NC/22-23-2021")
      (footprint "22-23-2021:22-23-2021")
      (description "Connector Header Through Hole 2 position 0.100 (2.54mm)")
      (fields (field (name "MP") "22232021") (field (name "MF") "Molex"))
      (libsource (lib "SamacSys") (part "22-23-2021"))
    )
    (comp (ref "J48")
      (value "NC/22-23-2021")
      (footprint "22-23-2021:22-23-2021")
      (description "Connector Header Through Hole 2 position 0.100 (2.54mm)")
      (fields (field (name "MP") "22232021") (field (name "MF") "Molex"))
      (libsource (lib "SamacSys") (part "22-23-2021"))
    )
    (comp (ref "J49")
      (value "NC/22-23-2041")
      (footprint "22-23-2041:22-23-2041")
      (description "Connector Header Through Hole 4 position 0.100 (2.54mm)")
      (fields (field (name "MF") "Molex") (field (name "MP") "22-23-2041"))
      (libsource (lib "SamacSys") (part "22-23-2041"))
    )
    (comp (ref "J51")
      (value "NC/22-23-2021")
      (footprint "22-23-2021:22-23-2021")
      (description "Connector Header Through Hole 2 position 0.100 (2.54mm)")
      (fields (field (name "MP") "22232021") (field (name "MF") "Molex"))
      (libsource (lib "SamacSys") (part "22-23-2021"))
    )
    (comp (ref "J52")
      (value "NC/22-23-2021")
      (footprint "22-23-2021:22-23-2021")
      (description "Connector Header Through Hole 2 position 0.100 (2.54mm)")
      (fields (field (name "MP") "22232021") (field (name "MF") "Molex"))
      (libsource (lib "SamacSys") (part "22-23-2021"))
    )
    (comp (ref "L2")
      (value "NC/600@100M")
      (footprint "L_0603_1608Metric")
      (description "CIM10J601NC")
      (fields (field (name "LIBRARYNAME") "inductors-jwmiller"))
      (libsource (lib "SamacSys") (part "FB-M1331"))
    )
    (comp (ref "L3")
      (value "600@100M")
      (footprint "L_0603_1608Metric")
      (description "BBPY00160808601Y00")
      (fields (field (name "LIBRARYNAME") "inductors-jwmiller"))
      (libsource (lib "SamacSys") (part "FB-M1331"))
    )
    (comp (ref "L4")
      (value "600@100M")
      (footprint "L_0603_1608Metric")
      (description "BBPY00160808601Y00")
      (fields (field (name "LIBRARYNAME") "inductors-jwmiller"))
      (libsource (lib "SamacSys") (part "FB-M1331"))
    )
    (comp (ref "L5")
      (value "NC/600@100M")
      (footprint "L_0603_1608Metric")
      (description "BBPY00160808601Y00")
      (fields (field (name "LIBRARYNAME") "inductors-jwmiller"))
      (libsource (lib "SamacSys") (part "FB-M1331"))
    )
    (comp (ref "L6")
      (value "NC/600@100M")
      (footprint "L_0603_1608Metric")
      (description "BBPY00160808601Y00")
      (fields (field (name "LIBRARYNAME") "inductors-jwmiller"))
      (libsource (lib "SamacSys") (part "FB-M1331"))
    )
    (comp (ref "L7")
      (value "NC/600@100M")
      (footprint "L_0603_1608Metric")
      (description "BBPY00160808601Y00")
      (fields (field (name "LIBRARYNAME") "inductors-jwmiller"))
      (libsource (lib "SamacSys") (part "FB-M1331"))
    )
    (comp (ref "L17")
      (value "600@100M")
      (footprint "L_0603_1608Metric")
      (description "BBPY00160808601Y00")
      (fields (field (name "LIBRARYNAME") "inductors-jwmiller"))
      (libsource (lib "SamacSys") (part "FB-M1331"))
    )
    (comp (ref "LED1")
      (value "150080VS75000")
      (footprint "LEDC2012X120N")
      (description "LED GREEN CLEAR 0805 SMD")
      (fields (field (name "MF") "Lumex Opto/Components") (field (name "MP") "SML-LXT0805IW-TR"))
      (libsource (lib "SamacSys") (part "SML-LXT0805IW-TR"))
    )
    (comp (ref "LED2")
      (value "150080VS75000")
      (footprint "LEDC2012X120N")
      (description "LED GREEN CLEAR 0805 SMD")
      (fields (field (name "MF") "Lumex Opto/Components") (field (name "MP") "SML-LXT0805IW-TR"))
      (libsource (lib "SamacSys") (part "SML-LXT0805IW-TR"))
    )
    (comp (ref "LED3")
      (value "150080VS75000")
      (footprint "LEDC2012X120N")
      (description "LED GREEN CLEAR 0805 SMD")
      (fields (field (name "MF") "Lumex Opto/Components") (field (name "MP") "SML-LXT0805IW-TR"))
      (libsource (lib "SamacSys") (part "SML-LXT0805IW-TR"))
    )
    (comp (ref "LED4")
      (value "150080VS75000")
      (footprint "LEDC2012X120N")
      (description "LED GREEN CLEAR 0805 SMD")
      (fields (field (name "MF") "Lumex Opto/Components") (field (name "MP") "SML-LXT0805IW-TR"))
      (libsource (lib "SamacSys") (part "SML-LXT0805IW-TR"))
    )
    (comp (ref "LED6")
      (value "150080SS75000")
      (footprint "LEDC2012X120N")
      (description "LED RED CLEAR 0805 SMD")
      (fields (field (name "MF") "Lumex Opto/Components") (field (name "MP") "SML-LXT0805IW-TR"))
      (libsource (lib "SamacSys") (part "SML-LXT0805IW-TR"))
    )
    (comp (ref "LED10")
      (value "150080SS75000")
      (footprint "LEDC2012X120N")
      (description "LED RED CLEAR 0805 SMD")
      (fields (field (name "MF") "Lumex Opto/Components") (field (name "MP") "SML-LXT0805IW-TR"))
      (libsource (lib "SamacSys") (part "SML-LXT0805IW-TR"))
    )
    (comp (ref "LED13")
      (value "150080VS75000")
      (footprint "LEDC2012X120N")
      (description "LED GREEN CLEAR 0805 SMD")
      (fields (field (name "MF") "Lumex Opto/Components") (field (name "MP") "SML-LXT0805IW-TR"))
      (libsource (lib "SamacSys") (part "SML-LXT0805IW-TR"))
    )
    (comp (ref "LED14")
      (value "150080VS75000")
      (footprint "LEDC2012X120N")
      (description "LED GREEN CLEAR 0805 SMD")
      (fields (field (name "MF") "Lumex Opto/Components") (field (name "MP") "SML-LXT0805IW-TR"))
      (libsource (lib "SamacSys") (part "SML-LXT0805IW-TR"))
    )
    (comp (ref "LED15")
      (value "150080VS75000")
      (footprint "LEDC2012X120N")
      (description "LED GREEN CLEAR 0805 SMD")
      (fields (field (name "MF") "Lumex Opto/Components") (field (name "MP") "SML-LXT0805IW-TR"))
      (libsource (lib "SamacSys") (part "SML-LXT0805IW-TR"))
    )
    (comp (ref "Q1")
      (value "PDTC114ET,215")
      (footprint "SOT95P230X110-3N")
      (description "TRANS PREBIAS NPN 250MW TO236AB")
      (libsource (lib "SamacSys") (part "PDTC114ET,215"))
    )
    (comp (ref "Q2")
      (value "PDTC114ET,215")
      (footprint "SOT95P230X110-3N")
      (description "TRANS PREBIAS NPN 250MW TO236AB")
      (libsource (lib "SamacSys") (part "PDTC114ET,215"))
    )
    (comp (ref "Q3")
      (value "PDTC114ET,215")
      (footprint "SOT95P230X110-3N")
      (description "TRANS PREBIAS NPN 250MW TO236AB")
      (libsource (lib "SamacSys") (part "PDTC114ET,215"))
    )
    (comp (ref "Q4")
      (value "PDTC114ET,215")
      (footprint "SOT95P230X110-3N")
      (description "TRANS PREBIAS NPN 250MW TO236AB")
      (libsource (lib "SamacSys") (part "PDTC114ET,215"))
    )
    (comp (ref "Q5")
      (value "PDTC114ET,215")
      (footprint "SOT95P230X110-3N")
      (description "TRANS PREBIAS NPN 250MW TO236AB")
      (libsource (lib "SamacSys") (part "PDTC114ET,215"))
    )
    (comp (ref "Q6")
      (value "NC/BC847B-7-F")
      (footprint "SOT95P230X110-3N")
      (libsource (lib "SamacSys") (part "BC847B-7-F"))
    )
    (comp (ref "Q7")
      (value "NC/BC847B-7-F")
      (footprint "SOT95P230X110-3N")
      (libsource (lib "SamacSys") (part "BC847B-7-F"))
    )
    (comp (ref "Q8")
      (value "PDTC114ET,215")
      (footprint "SOT95P230X110-3N")
      (description "TRANS PREBIAS NPN 250MW TO236AB")
      (libsource (lib "SamacSys") (part "PDTC114ET,215"))
    )
    (comp (ref "Q9")
      (value "PDTC114ET,215")
      (footprint "SOT95P230X110-3N")
      (description "TRANS PREBIAS NPN 250MW TO236AB")
      (libsource (lib "SamacSys") (part "PDTC114ET,215"))
    )
    (comp (ref "R1")
      (value "2K")
      (footprint "R_0603_1608Metric")
      (description "RES SMD 2K OHM 5% 1/10W 0603")
      (fields (field (name "PUBLISHER") "Altium Limited"))
      (libsource (lib "Miscellaneous Devices") (part "Res2"))
    )
    (comp (ref "R2")
      (value "2K")
      (footprint "R_0603_1608Metric")
      (description "RES SMD 2K OHM 5% 1/10W 0603")
      (fields (field (name "PUBLISHER") "Altium Limited"))
      (libsource (lib "Miscellaneous Devices") (part "Res2"))
    )
    (comp (ref "R3")
      (value "1.2K")
      (footprint "R_0603_1608Metric")
      (description "RES 1.2K OHM 5% 1/10W 0603")
      (fields (field (name "PUBLISHER") "Altium Limited"))
      (libsource (lib "Miscellaneous Devices") (part "Res2"))
    )
    (comp (ref "R4")
      (value "100R")
      (footprint "R_0603_1608Metric")
      (description "RES 100 OHM 5% 1/10W 0603")
      (libsource (lib "AT") (part "RES"))
    )
    (comp (ref "R5")
      (value "1K")
      (footprint "R_0603_1608Metric")
      (description "RES 1K OHM 5% 1/10W 0603")
      (fields (field (name "PUBLISHER") "Altium Limited"))
      (libsource (lib "Miscellaneous Devices") (part "Res2"))
    )
    (comp (ref "R6")
      (value "1K")
      (footprint "R_0603_1608Metric")
      (description "RES 1K OHM 5% 1/10W 0603")
      (fields (field (name "PUBLISHER") "Altium Limited"))
      (libsource (lib "Miscellaneous Devices") (part "Res2"))
    )
    (comp (ref "R7")
      (value "100R")
      (footprint "R_0603_1608Metric")
      (description "RES 100 OHM 5% 1/10W 0603")
      (libsource (lib "AT") (part "RES"))
    )
    (comp (ref "R8")
      (value "1K")
      (footprint "R_0603_1608Metric")
      (description "RES 1K OHM 5% 1/10W 0603")
      (fields (field (name "PUBLISHER") "Altium Limited"))
      (libsource (lib "Miscellaneous Devices") (part "Res2"))
    )
    (comp (ref "R9")
      (value "1K")
      (footprint "R_0603_1608Metric")
      (description "RES 1K OHM 5% 1/10W 0603")
      (fields (field (name "PUBLISHER") "Altium Limited"))
      (libsource (lib "Miscellaneous Devices") (part "Res2"))
    )
    (comp (ref "R10")
      (value "1K")
      (footprint "R_0603_1608Metric")
      (description "RES 1K OHM 5% 1/10W 0603")
      (fields (field (name "PUBLISHER") "Altium Limited"))
      (libsource (lib "Miscellaneous Devices") (part "Res2"))
    )
    (comp (ref "R11")
      (value "1.2K")
      (footprint "R_0603_1608Metric")
      (description "RES 1.2K OHM 5% 1/10W 0603")
      (fields (field (name "PUBLISHER") "Altium Limited"))
      (libsource (lib "Miscellaneous Devices") (part "Res2"))
    )
    (comp (ref "R12")
      (value "100R")
      (footprint "R_0603_1608Metric")
      (description "RES 100 OHM 5% 1/10W 0603")
      (libsource (lib "AT") (part "RES"))
    )
    (comp (ref "R13")
      (value "1K")
      (footprint "R_0603_1608Metric")
      (description "RES 1K OHM 5% 1/10W 0603")
      (fields (field (name "PUBLISHER") "Altium Limited"))
      (libsource (lib "Miscellaneous Devices") (part "Res2"))
    )
    (comp (ref "R14")
      (value "200K")
      (footprint "R_0603_1608Metric")
      (description "RES 100 OHM 5% 1/10W 0603")
      (libsource (lib "AT") (part "RES"))
    )
    (comp (ref "R15")
      (value "100R")
      (footprint "R_0603_1608Metric")
      (description "RES 100 OHM 5% 1/10W 0603")
      (libsource (lib "AT") (part "RES"))
    )
    (comp (ref "R16")
      (value "200K")
      (footprint "R_0603_1608Metric")
      (description "RES 100 OHM 5% 1/10W 0603")
      (libsource (lib "AT") (part "RES"))
    )
    (comp (ref "R17")
      (value "100R")
      (footprint "R_0603_1608Metric")
      (description "RES 100 OHM 5% 1/10W 0603")
      (libsource (lib "AT") (part "RES"))
    )
    (comp (ref "R18")
      (value "100R")
      (footprint "R_0603_1608Metric")
      (description "RES 100 OHM 5% 1/10W 0603")
      (libsource (lib "AT") (part "RES"))
    )
    (comp (ref "R19")
      (value "0R")
      (footprint "R_0603_1608Metric")
      (description "RES 0 OHM JUMPER 1/10W 0603")
      (libsource (lib "AT") (part "RES"))
    )
    (comp (ref "R20")
      (value "NC")
      (footprint "R_0603_1608Metric")
      (description "RES 100 OHM 5% 1/10W 0603")
      (libsource (lib "AT") (part "RES"))
    )
    (comp (ref "R21")
      (value "0R")
      (footprint "R_0603_1608Metric")
      (description "RES 0 OHM JUMPER 1/10W 0603")
      (libsource (lib "AT") (part "RES"))
    )
    (comp (ref "R22")
      (value "100R")
      (footprint "R_0603_1608Metric")
      (description "RES 100 OHM 5% 1/10W 0603")
      (libsource (lib "AT") (part "RES"))
    )
    (comp (ref "R23")
      (value "100R")
      (footprint "R_0603_1608Metric")
      (description "RES 100 OHM 5% 1/10W 0603")
      (libsource (lib "AT") (part "RES"))
    )
    (comp (ref "R24")
      (value "100R")
      (footprint "R_0603_1608Metric")
      (description "RES 100 OHM 5% 1/10W 0603")
      (libsource (lib "AT") (part "RES"))
    )
    (comp (ref "R25")
      (value "10K")
      (footprint "R_0603_1608Metric")
      (description "RES 10K OHM 5% 1/10W 0603")
      (fields (field (name "PUBLISHER") "Altium Limited"))
      (libsource (lib "") (part "Res2_3"))
    )
    (comp (ref "R26")
      (value "10K")
      (footprint "R_0603_1608Metric")
      (description "RES 10K OHM 5% 1/10W 0603")
      (fields (field (name "PUBLISHER") "Altium Limited"))
      (libsource (lib "Miscellaneous Devices") (part "Res2"))
    )
    (comp (ref "R27")
      (value "200K")
      (footprint "R_0603_1608Metric")
      (description "RES 100 OHM 5% 1/10W 0603")
      (libsource (lib "AT") (part "RES"))
    )
    (comp (ref "R28")
      (value "1K")
      (footprint "R_0603_1608Metric")
      (description "RES 1K OHM 5% 1/10W 0603")
      (fields (field (name "PUBLISHER") "Altium Limited"))
      (libsource (lib "") (part "Res2_2"))
    )
    (comp (ref "R29")
      (value "2K")
      (footprint "R_0603_1608Metric")
      (description "RES SMD 2K OHM 5% 1/10W 0603")
      (fields (field (name "PUBLISHER") "Altium Limited"))
      (libsource (lib "Miscellaneous Devices") (part "Res2"))
    )
    (comp (ref "R30")
      (value "1K")
      (footprint "R_0603_1608Metric")
      (description "RES 1K OHM 5% 1/10W 0603")
      (fields (field (name "PUBLISHER") "Altium Limited"))
      (libsource (lib "") (part "Res2_2"))
    )
    (comp (ref "R31")
      (value "100R")
      (footprint "R_0603_1608Metric")
      (description "RES 100 OHM 5% 1/10W 0603")
      (libsource (lib "AT") (part "RES"))
    )
    (comp (ref "R32")
      (value "200K")
      (footprint "R_0603_1608Metric")
      (description "RES 100 OHM 5% 1/10W 0603")
      (libsource (lib "AT") (part "RES"))
    )
    (comp (ref "R33")
      (value "100R")
      (footprint "R_0603_1608Metric")
      (description "RES 100 OHM 5% 1/10W 0603")
      (libsource (lib "AT") (part "RES"))
    )
    (comp (ref "R34")
      (value "2K")
      (footprint "R_0603_1608Metric")
      (description "RES SMD 2K OHM 5% 1/10W 0603")
      (fields (field (name "PUBLISHER") "Altium Limited"))
      (libsource (lib "Miscellaneous Devices") (part "Res2"))
    )
    (comp (ref "R35")
      (value "1.2K")
      (footprint "R_0603_1608Metric")
      (description "RES 1.2K OHM 5% 1/10W 0603")
      (fields (field (name "PUBLISHER") "Altium Limited"))
      (libsource (lib "Miscellaneous Devices") (part "Res2"))
    )
    (comp (ref "R36")
      (value "1.2K")
      (footprint "R_0603_1608Metric")
      (description "RES 1.2K OHM 5% 1/10W 0603")
      (fields (field (name "PUBLISHER") "Altium Limited"))
      (libsource (lib "Miscellaneous Devices") (part "Res2"))
    )
    (comp (ref "R37")
      (value "100R")
      (footprint "R_0603_1608Metric")
      (description "RES 100 OHM 5% 1/10W 0603")
      (libsource (lib "AT") (part "RES"))
    )
    (comp (ref "R38")
      (value "NC/4.7K")
      (footprint "R_0603_1608Metric")
      (description "CRCW08054K70FKEA")
      (fields (field (name "PUBLISHER") "Altium Limited"))
      (libsource (lib "Miscellaneous Devices") (part "Res2"))
    )
    (comp (ref "R39")
      (value "NC")
      (footprint "R_0603_1608Metric")
      (description "RES 100 OHM 5% 1/10W 0603")
      (libsource (lib "AT") (part "RES"))
    )
    (comp (ref "R40")
      (value "NC")
      (footprint "R_0603_1608Metric")
      (description "RES 100 OHM 5% 1/10W 0603")
      (libsource (lib "AT") (part "RES"))
    )
    (comp (ref "R41")
      (value "NC")
      (footprint "R_0603_1608Metric")
      (description "RES 100 OHM 5% 1/10W 0603")
      (libsource (lib "AT") (part "RES"))
    )
    (comp (ref "R42")
      (value "100R")
      (footprint "R_0603_1608Metric")
      (description "RES 100 OHM 5% 1/10W 0603")
      (libsource (lib "AT") (part "RES"))
    )
    (comp (ref "R43")
      (value "100R")
      (footprint "R_0603_1608Metric")
      (description "RES 100 OHM 5% 1/10W 0603")
      (libsource (lib "AT") (part "RES"))
    )
    (comp (ref "R44")
      (value "NC/4.7K")
      (footprint "R_0603_1608Metric")
      (description "CRCW08054K70FKEA")
      (fields (field (name "PUBLISHER") "Altium Limited"))
      (libsource (lib "") (part "Res2_3"))
    )
    (comp (ref "R45")
      (value "100R")
      (footprint "R_0603_1608Metric")
      (description "RES 100 OHM 5% 1/10W 0603")
      (libsource (lib "AT") (part "RES"))
    )
    (comp (ref "R46")
      (value "200K")
      (footprint "R_0603_1608Metric")
      (description "RES 100 OHM 5% 1/10W 0603")
      (libsource (lib "AT") (part "RES"))
    )
    (comp (ref "R47")
      (value "100R")
      (footprint "R_0603_1608Metric")
      (description "RES 100 OHM 5% 1/10W 0603")
      (libsource (lib "AT") (part "RES"))
    )
    (comp (ref "R48")
      (value "1K")
      (footprint "R_0603_1608Metric")
      (description "RES 1K OHM 5% 1/10W 0603")
      (fields (field (name "PUBLISHER") "Altium Limited"))
      (libsource (lib "") (part "Res2_1"))
    )
    (comp (ref "R49")
      (value "1K")
      (footprint "R_0603_1608Metric")
      (description "RES 1K OHM 5% 1/10W 0603")
      (fields (field (name "PUBLISHER") "Altium Limited"))
      (libsource (lib "") (part "Res2_1"))
    )
    (comp (ref "R50")
      (value "1K")
      (footprint "R_0603_1608Metric")
      (description "RES 1K OHM 5% 1/10W 0603")
      (fields (field (name "PUBLISHER") "Altium Limited"))
      (libsource (lib "") (part "Res2_1"))
    )
    (comp (ref "R51")
      (value "1K")
      (footprint "R_0603_1608Metric")
      (description "RES 1K OHM 5% 1/10W 0603")
      (fields (field (name "PUBLISHER") "Altium Limited"))
      (libsource (lib "") (part "Res2_1"))
    )
    (comp (ref "R52")
      (value "200K")
      (footprint "R_0603_1608Metric")
      (description "RES 100 OHM 5% 1/10W 0603")
      (libsource (lib "AT") (part "RES"))
    )
    (comp (ref "R53")
      (value "100R")
      (footprint "R_0603_1608Metric")
      (description "RES 100 OHM 5% 1/10W 0603")
      (libsource (lib "AT") (part "RES"))
    )
    (comp (ref "R54")
      (value "100R")
      (footprint "R_0603_1608Metric")
      (description "RES 100 OHM 5% 1/10W 0603")
      (libsource (lib "AT") (part "RES"))
    )
    (comp (ref "R55")
      (value "NC")
      (footprint "R_0603_1608Metric")
      (description "RES 100 OHM 5% 1/10W 0603")
      (libsource (lib "AT") (part "RES"))
    )
    (comp (ref "R56")
      (value "NC")
      (footprint "R_0603_1608Metric")
      (description "RES 100 OHM 5% 1/10W 0603")
      (libsource (lib "AT") (part "RES"))
    )
    (comp (ref "R57")
      (value "NC/100R")
      (footprint "R_0603_1608Metric")
      (description "RES 100 OHM 5% 1/10W 0603")
      (libsource (lib "AT") (part "RES"))
    )
    (comp (ref "R58")
      (value "NC/100R")
      (footprint "R_0603_1608Metric")
      (description "RES 100 OHM 5% 1/10W 0603")
      (libsource (lib "AT") (part "RES"))
    )
    (comp (ref "R59")
      (value "NC")
      (footprint "R_0603_1608Metric")
      (description "RES 100 OHM 5% 1/10W 0603")
      (libsource (lib "AT") (part "RES"))
    )
    (comp (ref "R60")
      (value "10K")
      (footprint "R_0603_1608Metric")
      (description "RES 10K OHM 5% 1/10W 0603")
      (fields (field (name "PUBLISHER") "Altium Limited"))
      (libsource (lib "") (part "Res2_2"))
    )
    (comp (ref "R61")
      (value "10K")
      (footprint "R_0603_1608Metric")
      (description "RES 10K OHM 5% 1/10W 0603")
      (fields (field (name "PUBLISHER") "Altium Limited"))
      (libsource (lib "") (part "Res2_2"))
    )
    (comp (ref "R62")
      (value "10K")
      (footprint "R_0603_1608Metric")
      (description "RES 10K OHM 5% 1/10W 0603")
      (fields (field (name "PUBLISHER") "Altium Limited"))
      (libsource (lib "") (part "Res2_2"))
    )
    (comp (ref "R63")
      (value "NC/10K")
      (footprint "R_0603_1608Metric")
      (description "RC0805FR-071KL")
      (libsource (lib "AT") (part "RES"))
    )
    (comp (ref "R64")
      (value "NC/10K")
      (footprint "R_0603_1608Metric")
      (description "RC0805FR-071KL")
      (libsource (lib "AT") (part "RES"))
    )
    (comp (ref "R65")
      (value "10K")
      (footprint "R_0603_1608Metric")
      (description "RES 10K OHM 5% 1/10W 0603")
      (fields (field (name "PUBLISHER") "Altium Limited"))
      (libsource (lib "") (part "Res2_3"))
    )
    (comp (ref "R66")
      (value "NC/100R")
      (footprint "R_0603_1608Metric")
      (description "RES 100 OHM 5% 1/10W 0603")
      (libsource (lib "AT") (part "RES"))
    )
    (comp (ref "R67")
      (value "NC/100R")
      (footprint "R_0603_1608Metric")
      (description "RES 100 OHM 5% 1/10W 0603")
      (libsource (lib "AT") (part "RES"))
    )
    (comp (ref "R68")
      (value "NC/100R")
      (footprint "R_0603_1608Metric")
      (description "RES 100 OHM 5% 1/10W 0603")
      (libsource (lib "AT") (part "RES"))
    )
    (comp (ref "R69")
      (value "NC/100R")
      (footprint "R_0603_1608Metric")
      (description "RES 100 OHM 5% 1/10W 0603")
      (libsource (lib "AT") (part "RES"))
    )
    (comp (ref "R70")
      (value "NC/100R")
      (footprint "R_0603_1608Metric")
      (description "RES 100 OHM 5% 1/10W 0603")
      (libsource (lib "AT") (part "RES"))
    )
    (comp (ref "R71")
      (value "NC/100R")
      (footprint "R_0603_1608Metric")
      (description "RES 100 OHM 5% 1/10W 0603")
      (libsource (lib "AT") (part "RES"))
    )
    (comp (ref "R72")
      (value "NC/100R")
      (footprint "R_0603_1608Metric")
      (description "RES 100 OHM 5% 1/10W 0603")
      (libsource (lib "AT") (part "RES"))
    )
    (comp (ref "R73")
      (value "10K")
      (footprint "R_0603_1608Metric")
      (description "RES 10K OHM 5% 1/10W 0603")
      (fields (field (name "PUBLISHER") "Altium Limited"))
      (libsource (lib "") (part "Res2_2"))
    )
    (comp (ref "R74")
      (value "NC/100R")
      (footprint "R_0603_1608Metric")
      (description "RES 100 OHM 5% 1/10W 0603")
      (libsource (lib "AT") (part "RES"))
    )
    (comp (ref "R75")
      (value "NC/100R")
      (footprint "R_0603_1608Metric")
      (description "RES 100 OHM 5% 1/10W 0603")
      (libsource (lib "AT") (part "RES"))
    )
    (comp (ref "R76")
      (value "NC/100R")
      (footprint "R_0603_1608Metric")
      (description "RES 100 OHM 5% 1/10W 0603")
      (libsource (lib "AT") (part "RES"))
    )
    (comp (ref "R77")
      (value "NC/100R")
      (footprint "R_0603_1608Metric")
      (description "RES 100 OHM 5% 1/10W 0603")
      (libsource (lib "AT") (part "RES"))
    )
    (comp (ref "R78")
      (value "NC/100R")
      (footprint "R_0603_1608Metric")
      (description "RES 100 OHM 5% 1/10W 0603")
      (libsource (lib "AT") (part "RES"))
    )
    (comp (ref "R79")
      (value "NC/100R")
      (footprint "R_0603_1608Metric")
      (description "RES 100 OHM 5% 1/10W 0603")
      (libsource (lib "AT") (part "RES"))
    )
    (comp (ref "R80")
      (value "NC/100R")
      (footprint "R_0603_1608Metric")
      (description "RES 100 OHM 5% 1/10W 0603")
      (libsource (lib "AT") (part "RES"))
    )
    (comp (ref "R81")
      (value "NC/10K")
      (footprint "R_0603_1608Metric")
      (description "RC0805FR-071KL")
      (libsource (lib "AT") (part "RES"))
    )
    (comp (ref "R82")
      (value "NC/10K")
      (footprint "R_0603_1608Metric")
      (description "RC0805FR-071KL")
      (libsource (lib "AT") (part "RES"))
    )
    (comp (ref "R83")
      (value "1K")
      (footprint "R_0603_1608Metric")
      (description "RES 1K OHM 5% 1/10W 0603")
      (fields (field (name "PUBLISHER") "Altium Limited"))
      (libsource (lib "") (part "Res2_3"))
    )
    (comp (ref "R84")
      (value "0R")
      (footprint "R_0603_1608Metric")
      (description "RES 0 OHM JUMPER 1/10W 0603")
      (libsource (lib "AT") (part "RES"))
    )
    (comp (ref "R85")
      (value "NC/10K")
      (footprint "R_0603_1608Metric")
      (description "RC0805FR-071KL")
      (libsource (lib "AT") (part "RES"))
    )
    (comp (ref "R86")
      (value "10K")
      (footprint "R_0603_1608Metric")
      (description "RES 10K OHM 5% 1/10W 0603")
      (fields (field (name "PUBLISHER") "Altium Limited"))
      (libsource (lib "") (part "Res2_2"))
    )
    (comp (ref "R87")
      (value "330K")
      (footprint "R_0603_1608Metric")
      (description "RES 330K OHM 5% 1/10W 0603")
      (libsource (lib "AT") (part "RES"))
    )
    (comp (ref "R88")
      (value "NC/10K")
      (footprint "R_0603_1608Metric")
      (description "RC0805FR-071KL")
      (libsource (lib "AT") (part "RES"))
    )
    (comp (ref "R89")
      (value "330K")
      (footprint "R_0603_1608Metric")
      (description "RES 330K OHM 5% 1/10W 0603")
      (libsource (lib "AT") (part "RES"))
    )
    (comp (ref "R90")
      (value "330K")
      (footprint "R_0603_1608Metric")
      (description "RES 330K OHM 5% 1/10W 0603")
      (libsource (lib "AT") (part "RES"))
    )
    (comp (ref "R91")
      (value "330K")
      (footprint "R_0603_1608Metric")
      (description "RES 330K OHM 5% 1/10W 0603")
      (libsource (lib "AT") (part "RES"))
    )
    (comp (ref "R92")
      (value "330K")
      (footprint "R_0603_1608Metric")
      (description "RES 330K OHM 5% 1/10W 0603")
      (libsource (lib "AT") (part "RES"))
    )
    (comp (ref "R93")
      (value "330K")
      (footprint "R_0603_1608Metric")
      (description "RES 330K OHM 5% 1/10W 0603")
      (libsource (lib "AT") (part "RES"))
    )
    (comp (ref "R94")
      (value "0R")
      (footprint "R_0603_1608Metric")
      (description "RES 0 OHM JUMPER 1/10W 0603")
      (libsource (lib "AT") (part "RES"))
    )
    (comp (ref "R95")
      (value "0R")
      (footprint "R_0603_1608Metric")
      (description "RES 0 OHM JUMPER 1/10W 0603")
      (libsource (lib "AT") (part "RES"))
    )
    (comp (ref "R96")
      (value "0R")
      (footprint "R_0603_1608Metric")
      (description "RES 0 OHM JUMPER 1/10W 0603")
      (libsource (lib "AT") (part "RES"))
    )
    (comp (ref "R98")
      (value "1K")
      (footprint "R_0603_1608Metric")
      (description "RES 1K OHM 5% 1/10W 0603")
      (fields (field (name "PUBLISHER") "Altium Limited"))
      (libsource (lib "") (part "Res2_1"))
    )
    (comp (ref "R101")
      (value "100K")
      (footprint "R_0603_1608Metric")
      (description "RES SMD 100K OHM 5% 1/10W 0603")
      (fields (field (name "PUBLISHER") "Altium Limited"))
      (libsource (lib "Miscellaneous Devices") (part "Res2"))
    )
    (comp (ref "R102")
      (value "NC/10K")
      (footprint "R_0603_1608Metric")
      (description "RC0805FR-071KL")
      (libsource (lib "AT") (part "RES"))
    )
    (comp (ref "R128")
      (value "10K")
      (footprint "R_0603_1608Metric")
      (description "RES 10K OHM 5% 1/10W 0603")
      (fields (field (name "PUBLISHER") "Altium Limited"))
      (libsource (lib "Miscellaneous Devices") (part "Res2"))
    )
    (comp (ref "R143")
      (value "NC/10K")
      (footprint "R_0603_1608Metric")
      (description "RC0805FR-071KL")
      (libsource (lib "AT") (part "RES"))
    )
    (comp (ref "R144")
      (value "NC/10K")
      (footprint "R_0603_1608Metric")
      (description "RC0805FR-071KL")
      (libsource (lib "AT") (part "RES"))
    )
    (comp (ref "R148")
      (value "NC/10K")
      (footprint "R_0603_1608Metric")
      (description "RC0805FR-071KL")
      (libsource (lib "AT") (part "RES"))
    )
    (comp (ref "R149")
      (value "NC/10K")
      (footprint "R_0603_1608Metric")
      (description "RC0805FR-071KL")
      (libsource (lib "AT") (part "RES"))
    )
    (comp (ref "R150")
      (value "NC/10K")
      (footprint "R_0603_1608Metric")
      (description "RC0805FR-071KL")
      (libsource (lib "AT") (part "RES"))
    )
    (comp (ref "R151")
      (value "NC/10K")
      (footprint "R_0603_1608Metric")
      (description "RC0805FR-071KL")
      (libsource (lib "AT") (part "RES"))
    )
    (comp (ref "R152")
      (value "NC/10K")
      (footprint "R_0603_1608Metric")
      (description "RC0805FR-071KL")
      (libsource (lib "AT") (part "RES"))
    )
    (comp (ref "R153")
      (value "NC/10K")
      (footprint "R_0603_1608Metric")
      (description "RC0805FR-071KL")
      (libsource (lib "AT") (part "RES"))
    )
    (comp (ref "R154")
      (value "NC/10K")
      (footprint "R_0603_1608Metric")
      (description "RC0805FR-071KL")
      (libsource (lib "AT") (part "RES"))
    )
    (comp (ref "R157")
      (value "10K")
      (footprint "R_0603_1608Metric")
      (description "RES 10K OHM 5% 1/10W 0603")
      (fields (field (name "PUBLISHER") "Altium Limited"))
      (libsource (lib "Miscellaneous Devices") (part "Res2"))
    )
    (comp (ref "R158")
      (value "10K")
      (footprint "R_0603_1608Metric")
      (description "RES 10K OHM 5% 1/10W 0603")
      (fields (field (name "PUBLISHER") "Altium Limited"))
      (libsource (lib "Miscellaneous Devices") (part "Res2"))
    )
    (comp (ref "R161")
      (value "10K")
      (footprint "R_0603_1608Metric")
      (description "RES 10K OHM 5% 1/10W 0603")
      (fields (field (name "PUBLISHER") "Altium Limited"))
      (libsource (lib "Miscellaneous Devices") (part "Res2"))
    )
    (comp (ref "R162")
      (value "10K")
      (footprint "R_0603_1608Metric")
      (description "RES 10K OHM 5% 1/10W 0603")
      (fields (field (name "PUBLISHER") "Altium Limited"))
      (libsource (lib "Miscellaneous Devices") (part "Res2"))
    )
    (comp (ref "R163")
      (value "100R")
      (footprint "R_0603_1608Metric")
      (description "RES 100 OHM 5% 1/10W 0603")
      (libsource (lib "AT") (part "RES"))
    )
    (comp (ref "R164")
      (value "100R")
      (footprint "R_0603_1608Metric")
      (description "RES 100 OHM 5% 1/10W 0603")
      (libsource (lib "AT") (part "RES"))
    )
    (comp (ref "R165")
      (value "100R")
      (footprint "R_0603_1608Metric")
      (description "RES 100 OHM 5% 1/10W 0603")
      (libsource (lib "AT") (part "RES"))
    )
    (comp (ref "R166")
      (value "100R")
      (footprint "R_0603_1608Metric")
      (description "RES 100 OHM 5% 1/10W 0603")
      (libsource (lib "AT") (part "RES"))
    )
    (comp (ref "R167")
      (value "NC/100R")
      (footprint "R_0603_1608Metric")
      (description "RES 100 OHM 5% 1/10W 0603")
      (fields (field (name "PUBLISHER") "Altium Limited"))
      (libsource (lib "") (part "Res2_1"))
    )
    (comp (ref "R168")
      (value "NC/100R")
      (footprint "R_0603_1608Metric")
      (description "RES 100 OHM 5% 1/10W 0603")
      (fields (field (name "PUBLISHER") "Altium Limited"))
      (libsource (lib "") (part "Res2_1"))
    )
    (comp (ref "R169")
      (value "NC/100R")
      (footprint "R_0603_1608Metric")
      (description "RES 100 OHM 5% 1/10W 0603")
      (fields (field (name "PUBLISHER") "Altium Limited"))
      (libsource (lib "") (part "Res2_1"))
    )
    (comp (ref "R170")
      (value "NC/100R")
      (footprint "R_0603_1608Metric")
      (description "RES 100 OHM 5% 1/10W 0603")
      (fields (field (name "PUBLISHER") "Altium Limited"))
      (libsource (lib "") (part "Res2_1"))
    )
    (comp (ref "RN1")
      (value "YC124-JR-0747RL")
      (footprint "RESCAXS50P200X100X55-8N")
      (description "RES ARRAY 4 RES 47 OHM 0804")
      (fields (field (name "MF") "Yageo") (field (name "MP") "TC164-JR-0747RL"))
      (libsource (lib "Zigbee Sch Lib_SJCH") (part "TC164-JR-0747RL"))
    )
    (comp (ref "RN3")
      (value "YC124-JR-0747RL")
      (footprint "RESCAXS50P200X100X55-8N")
      (description "RES ARRAY 4 RES 47 OHM 0804")
      (fields (field (name "MF") "Yageo") (field (name "MP") "TC164-JR-0747RL"))
      (libsource (lib "Zigbee Sch Lib_SJCH") (part "TC164-JR-0747RL"))
    )
    (comp (ref "S1")
      (value "KG04ET")
      (footprint "SW_DS01-254-S-04BE")
      (description "STANDARD DIP SWITCH, 4 POSITIONS")
      (fields (field (name "MP") "DS01-254-S-04BE") (field (name "MF") "CUI Devices"))
      (libsource (lib "SamacSys") (part "4 Position Dip Switch"))
    )
    (comp (ref "U1")
      (value "LTV-847S")
      (footprint "SMD-16 19.84X7.62MM P2.54mm")
      (description "OPTOISOLTR 5KV 4CH TRANS 16-SMD")
      (libsource (lib "Altium lib") (part "LTV-847S"))
    )
    (comp (ref "U2")
      (value "NC/USBLC6-2SC6")
      (footprint "SOT95P280X145-6N")
      (fields (field (name "MP") "USBLC6-2SC6") (field (name "MF") "STMicroelectronics"))
      (libsource (lib "SnapEDAsch") (part "USBLC6-2SC6"))
    )
    (comp (ref "U7")
      (value "SST26VF016BT-80E/SN")
      (footprint "SOIC-8")
      (description "IC FLASH 16MBIT SPI/QUAD 8SOIC")
      (libsource (lib "SamacSys") (part "MX25L6406EM2I-12G"))
    )
    (comp (ref "U8")
      (value "XBee3 through-hole module")
      (footprint "XB3-24Z8PT-J")
      (description "RECEPTACLE STRIP 10P 2.0MM PITCH")
      (fields (field (name "MP") "XB3-24Z8PT-J") (field (name "MF") "Digi International"))
      (libsource (lib "Altium lib") (part "XB3-24Z8PT-J"))
    )
    (comp (ref "U27")
      (value "BA033CC0FP-E2")
      (footprint "ROHM_TO-252-3")
      (description "LDO regulator,3.3V,1A,TO252")
      (fields (field (name "MOUSER PART NUMBER") "755-BA033CC0FP-E2"))
      (libsource (lib "Main Board V1.1") (part "BA033CC0FP-E2"))
    )
    (comp (ref "U33")
      (value "L78M05ABDT-TR")
      (footprint "VREG_L78M05ABDT-TR")
      (description "Linear Voltage Regulator IC 1 Output 500mA DPAK")
      (fields (field (name "MF") "STMicroelectronics"))
      (libsource (lib "Main Board V1.1") (part "L78M05ABDT-TR"))
    )
  )
  (nets
    (net (code "1") (name "/A_DECAY{slash}NPCS0") (class "Default")
      (node (ref "D10") (pin "5") (pinfunction "5_cathode_5") (pintype "passive"))
      (node (ref "J15") (pin "9") (pinfunction "9_9") (pintype "passive"))
      (node (ref "R16") (pin "1") (pinfunction "1_1") (pintype "passive"))
      (node (ref "R89") (pin "1") (pinfunction "1_1") (pintype "passive"))
    )
    (net (code "2") (name "/A_EN{slash}IN1") (class "Default")
      (node (ref "D10") (pin "3") (pinfunction "2_cathode_3") (pintype "passive"))
      (node (ref "J15") (pin "7") (pinfunction "7_7") (pintype "passive"))
      (node (ref "R17") (pin "2") (pinfunction "2_2") (pintype "passive"))
    )
    (net (code "3") (name "/A_MISO") (class "Default")
      (node (ref "D11") (pin "1") (pinfunction "1_cathode_1") (pintype "passive"))
      (node (ref "J15") (pin "2") (pinfunction "2_2") (pintype "passive"))
      (node (ref "R19") (pin "2") (pinfunction "2_2") (pintype "passive"))
    )
    (net (code "4") (name "/A_MOSI") (class "Default")
      (node (ref "D11") (pin "3") (pinfunction "2_cathode_3") (pintype "passive"))
      (node (ref "J15") (pin "1") (pinfunction "1_1") (pintype "passive"))
      (node (ref "R21") (pin "2") (pinfunction "2_2") (pintype "passive"))
    )
    (net (code "5") (name "/A_PH{slash}IN2") (class "Default")
      (node (ref "D10") (pin "1") (pinfunction "1_cathode_1") (pintype "passive"))
      (node (ref "J15") (pin "8") (pinfunction "8_8") (pintype "passive"))
      (node (ref "R15") (pin "2") (pinfunction "2_2") (pintype "passive"))
    )
    (net (code "6") (name "/A_SCL") (class "Default")
      (node (ref "D9") (pin "1") (pinfunction "1_cathode_1") (pintype "passive"))
      (node (ref "J15") (pin "12") (pinfunction "12_12") (pintype "passive"))
      (node (ref "R4") (pin "2") (pinfunction "2_2") (pintype "passive"))
    )
    (net (code "7") (name "/A_SDA") (class "Default")
      (node (ref "D9") (pin "3") (pinfunction "2_cathode_3") (pintype "passive"))
      (node (ref "J15") (pin "11") (pinfunction "11_11") (pintype "passive"))
      (node (ref "R12") (pin "2") (pinfunction "2_2") (pintype "passive"))
    )
    (net (code "8") (name "/A_SPCK") (class "Default")
      (node (ref "D11") (pin "5") (pinfunction "5_cathode_5") (pintype "passive"))
      (node (ref "J15") (pin "3") (pinfunction "3_3") (pintype "passive"))
      (node (ref "R20") (pin "1") (pinfunction "1_1") (pintype "passive"))
    )
    (net (code "9") (name "/A_TOFF") (class "Default")
      (node (ref "D9") (pin "4") (pinfunction "3_cathode_4") (pintype "passive"))
      (node (ref "J15") (pin "10") (pinfunction "10_10") (pintype "passive"))
      (node (ref "R14") (pin "1") (pinfunction "1_1") (pintype "passive"))
      (node (ref "R87") (pin "1") (pinfunction "1_1") (pintype "passive"))
    )
    (net (code "10") (name "/A_nFAULT") (class "Default")
      (node (ref "D9") (pin "5") (pinfunction "5_cathode_5") (pintype "passive"))
      (node (ref "J15") (pin "13") (pinfunction "13_13") (pintype "passive"))
      (node (ref "R7") (pin "1") (pinfunction "1_1") (pintype "passive"))
    )
    (net (code "11") (name "/A_nSLEEP") (class "Default")
      (node (ref "D10") (pin "4") (pinfunction "3_cathode_4") (pintype "passive"))
      (node (ref "J15") (pin "6") (pinfunction "6_6") (pintype "passive"))
      (node (ref "R18") (pin "1") (pinfunction "1_1") (pintype "passive"))
    )
    (net (code "12") (name "/B_DECAY{slash}NPCS2") (class "Default")
      (node (ref "D13") (pin "5") (pinfunction "5_cathode_5") (pintype "passive"))
      (node (ref "J16") (pin "9") (pinfunction "9_9") (pintype "passive"))
      (node (ref "R32") (pin "1") (pinfunction "1_1") (pintype "passive"))
      (node (ref "R91") (pin "1") (pinfunction "1_1") (pintype "passive"))
    )
    (net (code "13") (name "/B_EN{slash}IN1") (class "Default")
      (node (ref "D13") (pin "3") (pinfunction "2_cathode_3") (pintype "passive"))
      (node (ref "J16") (pin "7") (pinfunction "7_7") (pintype "passive"))
      (node (ref "R33") (pin "2") (pinfunction "2_2") (pintype "passive"))
    )
    (net (code "14") (name "/B_MISO") (class "Default")
      (node (ref "D14") (pin "1") (pinfunction "1_cathode_1") (pintype "passive"))
      (node (ref "J16") (pin "2") (pinfunction "2_2") (pintype "passive"))
      (node (ref "R39") (pin "2") (pinfunction "2_2") (pintype "passive"))
      (node (ref "R84") (pin "2") (pinfunction "2_2") (pintype "passive"))
    )
    (net (code "15") (name "/B_MOSI") (class "Default")
      (node (ref "D14") (pin "3") (pinfunction "2_cathode_3") (pintype "passive"))
      (node (ref "J16") (pin "1") (pinfunction "1_1") (pintype "passive"))
      (node (ref "R41") (pin "2") (pinfunction "2_2") (pintype "passive"))
      (node (ref "R95") (pin "2") (pinfunction "2_2") (pintype "passive"))
    )
    (net (code "16") (name "/B_PH{slash}IN2") (class "Default")
      (node (ref "D13") (pin "1") (pinfunction "1_cathode_1") (pintype "passive"))
      (node (ref "J16") (pin "8") (pinfunction "8_8") (pintype "passive"))
      (node (ref "R31") (pin "2") (pinfunction "2_2") (pintype "passive"))
    )
    (net (code "17") (name "/B_SCL") (class "Default")
      (node (ref "D12") (pin "1") (pinfunction "1_cathode_1") (pintype "passive"))
      (node (ref "J16") (pin "12") (pinfunction "12_12") (pintype "passive"))
      (node (ref "R22") (pin "2") (pinfunction "2_2") (pintype "passive"))
    )
    (net (code "18") (name "/B_SDA") (class "Default")
      (node (ref "D12") (pin "3") (pinfunction "2_cathode_3") (pintype "passive"))
      (node (ref "J16") (pin "11") (pinfunction "11_11") (pintype "passive"))
      (node (ref "R24") (pin "2") (pinfunction "2_2") (pintype "passive"))
    )
    (net (code "19") (name "/B_SPCK") (class "Default")
      (node (ref "D14") (pin "5") (pinfunction "5_cathode_5") (pintype "passive"))
      (node (ref "J16") (pin "3") (pinfunction "3_3") (pintype "passive"))
      (node (ref "R40") (pin "1") (pinfunction "1_1") (pintype "passive"))
    )
    (net (code "20") (name "/B_TOFF") (class "Default")
      (node (ref "D12") (pin "4") (pinfunction "3_cathode_4") (pintype "passive"))
      (node (ref "J16") (pin "10") (pinfunction "10_10") (pintype "passive"))
      (node (ref "R27") (pin "1") (pinfunction "1_1") (pintype "passive"))
      (node (ref "R90") (pin "1") (pinfunction "1_1") (pintype "passive"))
    )
    (net (code "21") (name "/B_nFAULT") (class "Default")
      (node (ref "D12") (pin "5") (pinfunction "5_cathode_5") (pintype "passive"))
      (node (ref "J16") (pin "13") (pinfunction "13_13") (pintype "passive"))
      (node (ref "R23") (pin "1") (pinfunction "1_1") (pintype "passive"))
    )
    (net (code "22") (name "/B_nSLEEP") (class "Default")
      (node (ref "D13") (pin "4") (pinfunction "3_cathode_4") (pintype "passive"))
      (node (ref "J16") (pin "6") (pinfunction "6_6") (pintype "passive"))
      (node (ref "R37") (pin "1") (pinfunction "1_1") (pintype "passive"))
    )
    (net (code "23") (name "/Black1") (class "Default")
      (node (ref "J7") (pin "1") (pinfunction "S_1") (pintype "passive"))
      (node (ref "U1") (pin "8") (pinfunction "4_Cathode_8") (pintype "passive"))
    )
    (net (code "24") (name "/Black2") (class "Default")
      (node (ref "J7") (pin "2") (pinfunction "S_2") (pintype "passive"))
      (node (ref "U1") (pin "1") (pinfunction "1_Anode_1") (pintype "passive"))
    )
    (net (code "25") (name "/Black3") (class "Default")
      (node (ref "J7") (pin "3") (pinfunction "S_3") (pintype "passive"))
      (node (ref "U1") (pin "4") (pinfunction "2_Cathode_4") (pintype "passive"))
    )
    (net (code "26") (name "/Black4") (class "Default")
      (node (ref "J7") (pin "4") (pinfunction "S_4") (pintype "passive"))
      (node (ref "U1") (pin "6") (pinfunction "3_Cathode_6") (pintype "passive"))
    )
    (net (code "27") (name "/CTS") (class "Default")
      (node (ref "RN1") (pin "4") (pinfunction "4_4") (pintype "passive"))
      (node (ref "U8") (pin "12") (pinfunction "~{CTS!/DIO7}_12") (pintype "bidirectional"))
    )
    (net (code "28") (name "/CTS0") (class "Default")
      (node (ref "J30") (pin "17") (pinfunction "17_17") (pintype "passive"))
      (node (ref "RN1") (pin "6") (pinfunction "6_6") (pintype "passive"))
    )
    (net (code "29") (name "/CTS1") (class "Default")
      (node (ref "J20") (pin "4") (pinfunction "4_4") (pintype "passive"))
      (node (ref "J33") (pin "26") (pinfunction "26_26") (pintype "passive"))
    )
    (net (code "30") (name "/CTS2") (class "Default")
      (node (ref "J21") (pin "4") (pinfunction "4_4") (pintype "passive"))
      (node (ref "J33") (pin "25") (pinfunction "25_25") (pintype "passive"))
    )
    (net (code "31") (name "/CTSJP1") (class "Default")
      (node (ref "J5") (pin "5") (pinfunction "S_5") (pintype "passive"))
      (node (ref "R167") (pin "1") (pinfunction "1_1") (pintype "passive"))
    )
    (net (code "32") (name "/C_DECAY{slash}NPCS1") (class "Default")
      (node (ref "D43") (pin "5") (pinfunction "5_cathode_5") (pintype "passive"))
      (node (ref "J17") (pin "9") (pinfunction "9_9") (pintype "passive"))
      (node (ref "R52") (pin "1") (pinfunction "1_1") (pintype "passive"))
      (node (ref "R93") (pin "1") (pinfunction "1_1") (pintype "passive"))
    )
    (net (code "33") (name "/C_EN{slash}IN1") (class "Default")
      (node (ref "D43") (pin "3") (pinfunction "2_cathode_3") (pintype "passive"))
      (node (ref "J17") (pin "7") (pinfunction "7_7") (pintype "passive"))
      (node (ref "R53") (pin "2") (pinfunction "2_2") (pintype "passive"))
    )
    (net (code "34") (name "/C_MISO") (class "Default")
      (node (ref "D44") (pin "1") (pinfunction "1_cathode_1") (pintype "passive"))
      (node (ref "J17") (pin "2") (pinfunction "2_2") (pintype "passive"))
      (node (ref "R55") (pin "2") (pinfunction "2_2") (pintype "passive"))
      (node (ref "R94") (pin "2") (pinfunction "2_2") (pintype "passive"))
    )
    (net (code "35") (name "/C_MOSI") (class "Default")
      (node (ref "D44") (pin "3") (pinfunction "2_cathode_3") (pintype "passive"))
      (node (ref "J17") (pin "1") (pinfunction "1_1") (pintype "passive"))
      (node (ref "R59") (pin "2") (pinfunction "2_2") (pintype "passive"))
      (node (ref "R96") (pin "2") (pinfunction "2_2") (pintype "passive"))
    )
    (net (code "36") (name "/C_PH{slash}IN2") (class "Default")
      (node (ref "D43") (pin "1") (pinfunction "1_cathode_1") (pintype "passive"))
      (node (ref "J17") (pin "8") (pinfunction "8_8") (pintype "passive"))
      (node (ref "R47") (pin "2") (pinfunction "2_2") (pintype "passive"))
    )
    (net (code "37") (name "/C_SCL") (class "Default")
      (node (ref "D42") (pin "1") (pinfunction "1_cathode_1") (pintype "passive"))
      (node (ref "J17") (pin "12") (pinfunction "12_12") (pintype "passive"))
      (node (ref "R42") (pin "2") (pinfunction "2_2") (pintype "passive"))
    )
    (net (code "38") (name "/C_SDA") (class "Default")
      (node (ref "D42") (pin "3") (pinfunction "2_cathode_3") (pintype "passive"))
      (node (ref "J17") (pin "11") (pinfunction "11_11") (pintype "passive"))
      (node (ref "R45") (pin "2") (pinfunction "2_2") (pintype "passive"))
    )
    (net (code "39") (name "/C_SPCK") (class "Default")
      (node (ref "D44") (pin "5") (pinfunction "5_cathode_5") (pintype "passive"))
      (node (ref "J17") (pin "3") (pinfunction "3_3") (pintype "passive"))
      (node (ref "R56") (pin "1") (pinfunction "1_1") (pintype "passive"))
    )
    (net (code "40") (name "/C_TOFF") (class "Default")
      (node (ref "D42") (pin "4") (pinfunction "3_cathode_4") (pintype "passive"))
      (node (ref "J17") (pin "10") (pinfunction "10_10") (pintype "passive"))
      (node (ref "R46") (pin "1") (pinfunction "1_1") (pintype "passive"))
      (node (ref "R92") (pin "1") (pinfunction "1_1") (pintype "passive"))
    )
    (net (code "41") (name "/C_nFAULT") (class "Default")
      (node (ref "D42") (pin "5") (pinfunction "5_cathode_5") (pintype "passive"))
      (node (ref "J17") (pin "13") (pinfunction "13_13") (pintype "passive"))
      (node (ref "R43") (pin "1") (pinfunction "1_1") (pintype "passive"))
    )
    (net (code "42") (name "/C_nSLEEP") (class "Default")
      (node (ref "D43") (pin "4") (pinfunction "3_cathode_4") (pintype "passive"))
      (node (ref "J17") (pin "6") (pinfunction "6_6") (pintype "passive"))
      (node (ref "R54") (pin "1") (pinfunction "1_1") (pintype "passive"))
    )
    (net (code "43") (name "/DIN") (class "Default")
      (node (ref "S1") (pin "1A") (pinfunction "COM1_1A") (pintype "passive"))
      (node (ref "S1") (pin "2A") (pinfunction "COM2_2A") (pintype "passive"))
      (node (ref "U8") (pin "3") (pinfunction "DIN/!CONFIG!/DIO14_3") (pintype "bidirectional"))
    )
    (net (code "44") (name "/DIO5") (class "Default")
      (node (ref "R30") (pin "1") (pinfunction "1_1") (pintype "passive"))
      (node (ref "U8") (pin "15") (pinfunction "ASSOCIATE/DIO5_15") (pintype "bidirectional"))
    )
    (net (code "45") (name "/DIO10") (class "Default")
      (node (ref "R28") (pin "1") (pinfunction "1_1") (pintype "passive"))
      (node (ref "U8") (pin "6") (pinfunction "RSSI_PWM/DIO10_6") (pintype "bidirectional"))
    )
    (net (code "46") (name "/DIR-") (class "Default")
      (node (ref "J8") (pin "6") (pinfunction "6_6") (pintype "passive"))
      (node (ref "Q8") (pin "3") (pinfunction "output(collector)_3") (pintype "passive"))
    )
    (net (code "47") (name "/DOUT") (class "Default")
      (node (ref "S1") (pin "3A") (pinfunction "COM3_3A") (pintype "passive"))
      (node (ref "S1") (pin "4A") (pinfunction "COM4_4A") (pintype "passive"))
      (node (ref "U8") (pin "2") (pinfunction "DOUT/DIO13_2") (pintype "bidirectional"))
    )
    (net (code "48") (name "/DTR") (class "Default")
      (node (ref "R83") (pin "1") (pinfunction "1_1") (pintype "passive"))
      (node (ref "U8") (pin "9") (pinfunction "~{DTR!/SLEEP_RQ/DIO8}_9") (pintype "bidirectional"))
    )
    (net (code "49") (name "/ENA-") (class "Default")
      (node (ref "J8") (pin "8") (pinfunction "8_8") (pintype "passive"))
      (node (ref "Q9") (pin "3") (pinfunction "output(collector)_3") (pintype "passive"))
    )
    (net (code "50") (name "/HSD_N") (class "Default")
      (node (ref "J1") (pin "2") (pinfunction "D-_2") (pintype "bidirectional"))
      (node (ref "J31") (pin "3") (pinfunction "3_3") (pintype "passive"))
      (node (ref "J31") (pin "4") (pinfunction "4_4") (pintype "passive"))
      (node (ref "U2") (pin "1") (pinfunction "I/O1_1") (pintype "bidirectional"))
      (node (ref "U2") (pin "6") (pinfunction "I/O1_6") (pintype "bidirectional"))
    )
    (net (code "51") (name "/HSD_P") (class "Default")
      (node (ref "J1") (pin "3") (pinfunction "D+_3") (pintype "bidirectional"))
      (node (ref "J31") (pin "1") (pinfunction "1_1") (pintype "passive"))
      (node (ref "J31") (pin "2") (pinfunction "2_2") (pintype "passive"))
      (node (ref "U2") (pin "3") (pinfunction "I/O2_3") (pintype "bidirectional"))
      (node (ref "U2") (pin "4") (pinfunction "I/O2_4") (pintype "bidirectional"))
    )
    (net (code "52") (name "/MCCDA") (class "Default")
      (node (ref "J28") (pin "3") (pinfunction "CMD_3") (pintype "bidirectional"))
      (node (ref "J32") (pin "6") (pinfunction "6_6") (pintype "passive"))
      (node (ref "R62") (pin "2") (pinfunction "2_2") (pintype "passive"))
      (node (ref "RN3") (pin "3") (pinfunction "3_3") (pintype "passive"))
    )
    (net (code "53") (name "/MCCK") (class "Default")
      (node (ref "J28") (pin "5") (pinfunction "CLK_5") (pintype "bidirectional"))
      (node (ref "J32") (pin "7") (pinfunction "7_7") (pintype "passive"))
      (node (ref "R86") (pin "2") (pinfunction "2_2") (pintype "passive"))
      (node (ref "RN3") (pin "4") (pinfunction "4_4") (pintype "passive"))
    )
    (net (code "54") (name "/MCDA0") (class "Default")
      (node (ref "J28") (pin "7") (pinfunction "DAT0_7") (pintype "bidirectional"))
      (node (ref "J31") (pin "33") (pinfunction "33_33") (pintype "passive"))
      (node (ref "R128") (pin "1") (pinfunction "1_1") (pintype "passive"))
      (node (ref "RN3") (pin "1") (pinfunction "1_1") (pintype "passive"))
    )
    (net (code "55") (name "/MCDA1") (class "Default")
      (node (ref "J28") (pin "8") (pinfunction "DAT1_8") (pintype "bidirectional"))
      (node (ref "J32") (pin "5") (pinfunction "5_5") (pintype "passive"))
      (node (ref "R73") (pin "2") (pinfunction "2_2") (pintype "passive"))
    )
    (net (code "56") (name "/MCDA2") (class "Default")
      (node (ref "J28") (pin "1") (pinfunction "DAT2_1") (pintype "bidirectional"))
      (node (ref "J32") (pin "10") (pinfunction "10_10") (pintype "passive"))
      (node (ref "R60") (pin "2") (pinfunction "2_2") (pintype "passive"))
    )
    (net (code "57") (name "/MCDA3") (class "Default")
      (node (ref "J28") (pin "2") (pinfunction "CD/DAT3_2") (pintype "bidirectional"))
      (node (ref "J32") (pin "8") (pinfunction "8_8") (pintype "passive"))
      (node (ref "R61") (pin "2") (pinfunction "2_2") (pintype "passive"))
      (node (ref "RN3") (pin "2") (pinfunction "2_2") (pintype "passive"))
    )
    (net (code "58") (name "/MCDETECT") (class "Default")
      (node (ref "J28") (pin "SWA") (pinfunction "A_SWA") (pintype "bidirectional"))
      (node (ref "J32") (pin "9") (pinfunction "9_9") (pintype "passive"))
      (node (ref "R65") (pin "2") (pinfunction "2_2") (pintype "passive"))
    )
    (net (code "59") (name "/PA0") (class "Default")
      (node (ref "J32") (pin "11") (pinfunction "11_11") (pintype "passive"))
      (node (ref "R33") (pin "1") (pinfunction "1_1") (pintype "passive"))
    )
    (net (code "60") (name "/PA1") (class "Default")
      (node (ref "J32") (pin "14") (pinfunction "14_14") (pintype "passive"))
      (node (ref "R31") (pin "1") (pinfunction "1_1") (pintype "passive"))
    )
    (net (code "61") (name "/PA2") (class "Default")
      (node (ref "J32") (pin "28") (pinfunction "28_28") (pintype "passive"))
      (node (ref "R17") (pin "1") (pinfunction "1_1") (pintype "passive"))
    )
    (net (code "62") (name "/PA6") (class "Default")
      (node (ref "J31") (pin "27") (pinfunction "27_27") (pintype "passive"))
      (node (ref "U8") (pin "19") (pinfunction "AD1/DIO1/SPI_!ATTN!/I2C_SCL_19") (pintype "bidirectional"))
    )
    (net (code "63") (name "/PA15") (class "Default")
      (node (ref "J20") (pin "7") (pinfunction "7_7") (pintype "passive"))
      (node (ref "J33") (pin "32") (pinfunction "32_32") (pintype "passive"))
    )
    (net (code "64") (name "/PA16{slash}LED3") (class "Default")
      (node (ref "J33") (pin "13") (pinfunction "13_13") (pintype "passive"))
      (node (ref "Q4") (pin "1") (pinfunction "input(base)_1") (pintype "passive"))
    )
    (net (code "65") (name "/PA18") (class "Default")
      (node (ref "J33") (pin "10") (pinfunction "10_10") (pintype "passive"))
      (node (ref "R96") (pin "1") (pinfunction "1_1") (pintype "passive"))
    )
    (net (code "66") (name "/PA19") (class "Default")
      (node (ref "J30") (pin "19") (pinfunction "19_19") (pintype "passive"))
      (node (ref "R2") (pin "1") (pinfunction "1_1") (pintype "passive"))
      (node (ref "U1") (pin "14") (pinfunction "C_14") (pintype "passive"))
    )
    (net (code "67") (name "/PA20") (class "Default")
      (node (ref "J30") (pin "18") (pinfunction "18_18") (pintype "passive"))
      (node (ref "R93") (pin "2") (pinfunction "2_2") (pintype "passive"))
    )
    (net (code "68") (name "/PA22") (class "Default")
      (node (ref "C58") (pin "2") (pinfunction "2_2") (pintype "passive"))
      (node (ref "J30") (pin "28") (pinfunction "28_28") (pintype "passive"))
      (node (ref "R50") (pin "1") (pinfunction "1_1") (pintype "passive"))
    )
    (net (code "69") (name "/PA23") (class "Default")
      (node (ref "J21") (pin "6") (pinfunction "6_6") (pintype "passive"))
      (node (ref "J33") (pin "29") (pinfunction "29_29") (pintype "passive"))
    )
    (net (code "70") (name "/PA29") (class "Default")
      (node (ref "D8") (pin "4") (pinfunction "3_cathode_4") (pintype "passive"))
      (node (ref "J3") (pin "5") (pinfunction "5_5") (pintype "passive"))
      (node (ref "J31") (pin "13") (pinfunction "13_13") (pintype "passive"))
    )
    (net (code "71") (name "/PB6") (class "Default")
      (node (ref "C72") (pin "1") (pinfunction "1_1") (pintype "passive"))
      (node (ref "J31") (pin "29") (pinfunction "29_29") (pintype "passive"))
      (node (ref "R67") (pin "1") (pinfunction "1_1") (pintype "passive"))
    )
    (net (code "72") (name "/PB6_IO") (class "Default")
      (node (ref "D24") (pin "2") (pinfunction "C2_2") (pintype "passive"))
      (node (ref "J29") (pin "3") (pinfunction "3_3") (pintype "passive"))
      (node (ref "R154") (pin "1") (pinfunction "1_1") (pintype "passive"))
      (node (ref "R75") (pin "2") (pinfunction "2_2") (pintype "passive"))
    )
    (net (code "73") (name "/PB12") (class "Default")
      (node (ref "J33") (pin "34") (pinfunction "34_34") (pintype "passive"))
      (node (ref "R15") (pin "1") (pinfunction "1_1") (pintype "passive"))
    )
    (net (code "74") (name "/PB13") (class "Default")
      (node (ref "J30") (pin "5") (pinfunction "5_5") (pintype "passive"))
      (node (ref "R168") (pin "1") (pinfunction "1_1") (pintype "passive"))
    )
    (net (code "75") (name "/PC0{slash}NTC") (class "Default")
      (node (ref "J3") (pin "1") (pinfunction "1_1") (pintype "passive"))
      (node (ref "J30") (pin "12") (pinfunction "12_12") (pintype "passive"))
    )
    (net (code "76") (name "/PC1") (class "Default")
      (node (ref "C59") (pin "2") (pinfunction "2_2") (pintype "passive"))
      (node (ref "J30") (pin "27") (pinfunction "27_27") (pintype "passive"))
      (node (ref "R51") (pin "1") (pinfunction "1_1") (pintype "passive"))
    )
    (net (code "77") (name "/PC2") (class "Default")
      (node (ref "J33") (pin "15") (pinfunction "15_15") (pintype "passive"))
      (node (ref "R98") (pin "1") (pinfunction "1_1") (pintype "passive"))
    )
    (net (code "78") (name "/PC3") (class "Default")
      (node (ref "J21") (pin "7") (pinfunction "7_7") (pintype "passive"))
      (node (ref "J33") (pin "30") (pinfunction "30_30") (pintype "passive"))
    )
    (net (code "79") (name "/PC4{slash}LED2") (class "Default")
      (node (ref "J33") (pin "12") (pinfunction "12_12") (pintype "passive"))
      (node (ref "Q3") (pin "1") (pinfunction "input(base)_1") (pintype "passive"))
    )
    (net (code "80") (name "/PC5{slash}LED1") (class "Default")
      (node (ref "J33") (pin "7") (pinfunction "7_7") (pintype "passive"))
      (node (ref "Q2") (pin "1") (pinfunction "input(base)_1") (pintype "passive"))
    )
    (net (code "81") (name "/PC6") (class "Default")
      (node (ref "J33") (pin "16") (pinfunction "16_16") (pintype "passive"))
      (node (ref "R38") (pin "2") (pinfunction "2_2") (pintype "passive"))
      (node (ref "R44") (pin "2") (pinfunction "2_2") (pintype "passive"))
    )
    (net (code "82") (name "/PC7{slash}LED4") (class "Default")
      (node (ref "J33") (pin "14") (pinfunction "14_14") (pintype "passive"))
      (node (ref "Q5") (pin "1") (pinfunction "input(base)_1") (pintype "passive"))
    )
    (net (code "83") (name "/PC8") (class "Default")
      (node (ref "J32") (pin "26") (pinfunction "26_26") (pintype "passive"))
      (node (ref "R18") (pin "2") (pinfunction "2_2") (pintype "passive"))
    )
    (net (code "84") (name "/PC9") (class "Default")
      (node (ref "J20") (pin "6") (pinfunction "6_6") (pintype "passive"))
      (node (ref "J32") (pin "27") (pinfunction "27_27") (pintype "passive"))
    )
    (net (code "85") (name "/PC10") (class "Default")
      (node (ref "J32") (pin "29") (pinfunction "29_29") (pintype "passive"))
      (node (ref "R92") (pin "2") (pinfunction "2_2") (pintype "passive"))
    )
    (net (code "86") (name "/PC11") (class "Default")
      (node (ref "J32") (pin "15") (pinfunction "15_15") (pintype "passive"))
      (node (ref "R90") (pin "2") (pinfunction "2_2") (pintype "passive"))
    )
    (net (code "87") (name "/PC12") (class "Default")
      (node (ref "J30") (pin "11") (pinfunction "11_11") (pintype "passive"))
    )
    (net (code "88") (name "/PC13") (class "Default")
      (node (ref "J33") (pin "9") (pinfunction "9_9") (pintype "passive"))
      (node (ref "R34") (pin "1") (pinfunction "1_1") (pintype "passive"))
      (node (ref "U1") (pin "10") (pinfunction "C_10") (pintype "passive"))
    )
    (net (code "89") (name "/PC14") (class "Default")
      (node (ref "J32") (pin "25") (pinfunction "25_25") (pintype "passive"))
      (node (ref "R54") (pin "2") (pinfunction "2_2") (pintype "passive"))
    )
    (net (code "90") (name "/PC15") (class "Default")
      (node (ref "J30") (pin "13") (pinfunction "13_13") (pintype "passive"))
      (node (ref "R1") (pin "1") (pinfunction "1_1") (pintype "passive"))
      (node (ref "U1") (pin "16") (pinfunction "C_16") (pintype "passive"))
    )
    (net (code "91") (name "/PC16") (class "Default")
      (node (ref "J32") (pin "17") (pinfunction "17_17") (pintype "passive"))
      (node (ref "R23") (pin "2") (pinfunction "2_2") (pintype "passive"))
    )
    (net (code "92") (name "/PC17") (class "Default")
      (node (ref "J32") (pin "13") (pinfunction "13_13") (pintype "passive"))
      (node (ref "R91") (pin "2") (pinfunction "2_2") (pintype "passive"))
    )
    (net (code "93") (name "/PC18") (class "Default")
      (node (ref "C73") (pin "1") (pinfunction "1_1") (pintype "passive"))
      (node (ref "J31") (pin "30") (pinfunction "30_30") (pintype "passive"))
      (node (ref "R68") (pin "1") (pinfunction "1_1") (pintype "passive"))
    )
    (net (code "94") (name "/PC18_IO") (class "Default")
      (node (ref "D24") (pin "1") (pinfunction "C1_1") (pintype "passive"))
      (node (ref "J29") (pin "4") (pinfunction "4_4") (pintype "passive"))
      (node (ref "R153") (pin "1") (pinfunction "1_1") (pintype "passive"))
      (node (ref "R76") (pin "2") (pinfunction "2_2") (pintype "passive"))
    )
    (net (code "95") (name "/PC19") (class "Default")
      (node (ref "J31") (pin "28") (pinfunction "28_28") (pintype "passive"))
      (node (ref "U8") (pin "20") (pinfunction "AD0/DIO0_20") (pintype "bidirectional"))
    )
    (net (code "96") (name "/PC20") (class "Default")
      (node (ref "C76") (pin "1") (pinfunction "1_1") (pintype "passive"))
      (node (ref "J32") (pin "3") (pinfunction "3_3") (pintype "passive"))
      (node (ref "R71") (pin "1") (pinfunction "1_1") (pintype "passive"))
    )
    (net (code "97") (name "/PC20_IO") (class "Default")
      (node (ref "D26") (pin "2") (pinfunction "C2_2") (pintype "passive"))
      (node (ref "J29") (pin "7") (pinfunction "7_7") (pintype "passive"))
      (node (ref "R150") (pin "1") (pinfunction "1_1") (pintype "passive"))
      (node (ref "R79") (pin "2") (pinfunction "2_2") (pintype "passive"))
    )
    (net (code "98") (name "/PC21") (class "Default")
      (node (ref "J31") (pin "15") (pinfunction "15_15") (pintype "passive"))
      (node (ref "R7") (pin "2") (pinfunction "2_2") (pintype "passive"))
    )
    (net (code "99") (name "/PC22") (class "Default")
      (node (ref "J31") (pin "16") (pinfunction "16_16") (pintype "passive"))
      (node (ref "R47") (pin "1") (pinfunction "1_1") (pintype "passive"))
    )
    (net (code "100") (name "/PC23") (class "Default")
      (node (ref "C70") (pin "1") (pinfunction "1_1") (pintype "passive"))
      (node (ref "J31") (pin "31") (pinfunction "31_31") (pintype "passive"))
      (node (ref "R58") (pin "1") (pinfunction "1_1") (pintype "passive"))
    )
    (net (code "101") (name "/PC23_IO") (class "Default")
      (node (ref "D23") (pin "2") (pinfunction "C2_2") (pintype "passive"))
      (node (ref "J29") (pin "1") (pinfunction "1_1") (pintype "passive"))
      (node (ref "R57") (pin "2") (pinfunction "2_2") (pintype "passive"))
      (node (ref "R64") (pin "1") (pinfunction "1_1") (pintype "passive"))
    )
    (net (code "102") (name "/PC29") (class "Default")
      (node (ref "J30") (pin "10") (pinfunction "10_10") (pintype "passive"))
    )
    (net (code "103") (name "/PC30") (class "Default")
      (node (ref "J33") (pin "8") (pinfunction "8_8") (pintype "passive"))
      (node (ref "R29") (pin "1") (pinfunction "1_1") (pintype "passive"))
      (node (ref "U1") (pin "12") (pinfunction "C_12") (pintype "passive"))
    )
    (net (code "104") (name "/PC31") (class "Default")
      (node (ref "D7") (pin "1") (pinfunction "1_cathode_1") (pintype "passive"))
      (node (ref "J3") (pin "6") (pinfunction "6_6") (pintype "passive"))
      (node (ref "J30") (pin "14") (pinfunction "14_14") (pintype "passive"))
    )
    (net (code "105") (name "/PD0") (class "Default")
      (node (ref "J30") (pin "6") (pinfunction "6_6") (pintype "passive"))
      (node (ref "Q9") (pin "1") (pinfunction "input(base)_1") (pintype "passive"))
    )
    (net (code "106") (name "/PD1") (class "Default")
      (node (ref "J31") (pin "17") (pinfunction "17_17") (pintype "passive"))
      (node (ref "R14") (pin "2") (pinfunction "2_2") (pintype "passive"))
    )
    (net (code "107") (name "/PD2") (class "Default")
      (node (ref "D8") (pin "3") (pinfunction "2_cathode_3") (pintype "passive"))
      (node (ref "J3") (pin "4") (pinfunction "4_4") (pintype "passive"))
      (node (ref "J31") (pin "14") (pinfunction "14_14") (pintype "passive"))
    )
    (net (code "108") (name "/PD3") (class "Default")
      (node (ref "J31") (pin "20") (pinfunction "20_20") (pintype "passive"))
      (node (ref "R89") (pin "2") (pinfunction "2_2") (pintype "passive"))
    )
    (net (code "109") (name "/PD4") (class "Default")
      (node (ref "C71") (pin "1") (pinfunction "1_1") (pintype "passive"))
      (node (ref "J31") (pin "32") (pinfunction "32_32") (pintype "passive"))
      (node (ref "R66") (pin "1") (pinfunction "1_1") (pintype "passive"))
    )
    (net (code "110") (name "/PD4_IO") (class "Default")
      (node (ref "D23") (pin "1") (pinfunction "C1_1") (pintype "passive"))
      (node (ref "J29") (pin "2") (pinfunction "2_2") (pintype "passive"))
      (node (ref "R148") (pin "1") (pinfunction "1_1") (pintype "passive"))
      (node (ref "R74") (pin "2") (pinfunction "2_2") (pintype "passive"))
    )
    (net (code "111") (name "/PD5") (class "Default")
      (node (ref "J31") (pin "26") (pinfunction "26_26") (pintype "passive"))
      (node (ref "U8") (pin "5") (pinfunction "~{RESET}_5") (pintype "input"))
    )
    (net (code "112") (name "/PD6") (class "Default")
      (node (ref "J31") (pin "25") (pinfunction "25_25") (pintype "passive"))
      (node (ref "Q1") (pin "1") (pinfunction "input(base)_1") (pintype "passive"))
    )
    (net (code "113") (name "/PD7") (class "Default")
      (node (ref "J31") (pin "18") (pinfunction "18_18") (pintype "passive"))
      (node (ref "Q8") (pin "1") (pinfunction "input(base)_1") (pintype "passive"))
    )
    (net (code "114") (name "/PD8") (class "Default")
      (node (ref "C74") (pin "1") (pinfunction "1_1") (pintype "passive"))
      (node (ref "J32") (pin "1") (pinfunction "1_1") (pintype "passive"))
      (node (ref "R69") (pin "1") (pinfunction "1_1") (pintype "passive"))
    )
    (net (code "115") (name "/PD8_IO") (class "Default")
      (node (ref "D25") (pin "2") (pinfunction "C2_2") (pintype "passive"))
      (node (ref "J29") (pin "5") (pinfunction "5_5") (pintype "passive"))
      (node (ref "R152") (pin "1") (pinfunction "1_1") (pintype "passive"))
      (node (ref "R77") (pin "2") (pinfunction "2_2") (pintype "passive"))
    )
    (net (code "116") (name "/PD9") (class "Default")
      (node (ref "C75") (pin "1") (pinfunction "1_1") (pintype "passive"))
      (node (ref "J32") (pin "2") (pinfunction "2_2") (pintype "passive"))
      (node (ref "R70") (pin "1") (pinfunction "1_1") (pintype "passive"))
    )
    (net (code "117") (name "/PD9_IO") (class "Default")
      (node (ref "D25") (pin "1") (pinfunction "C1_1") (pintype "passive"))
      (node (ref "J29") (pin "6") (pinfunction "6_6") (pintype "passive"))
      (node (ref "R151") (pin "1") (pinfunction "1_1") (pintype "passive"))
      (node (ref "R78") (pin "2") (pinfunction "2_2") (pintype "passive"))
    )
    (net (code "118") (name "/PD11") (class "Default")
      (node (ref "J32") (pin "12") (pinfunction "12_12") (pintype "passive"))
      (node (ref "R37") (pin "2") (pinfunction "2_2") (pintype "passive"))
    )
    (net (code "119") (name "/PD13") (class "Default")
      (node (ref "J32") (pin "18") (pinfunction "18_18") (pintype "passive"))
      (node (ref "R27") (pin "2") (pinfunction "2_2") (pintype "passive"))
    )
    (net (code "120") (name "/PD14") (class "Default")
      (node (ref "J32") (pin "31") (pinfunction "31_31") (pintype "passive"))
      (node (ref "R43") (pin "2") (pinfunction "2_2") (pintype "passive"))
    )
    (net (code "121") (name "/PD17") (class "Default")
      (node (ref "J32") (pin "32") (pinfunction "32_32") (pintype "passive"))
      (node (ref "R46") (pin "2") (pinfunction "2_2") (pintype "passive"))
    )
    (net (code "122") (name "/PD23") (class "Default")
      (node (ref "J33") (pin "31") (pinfunction "31_31") (pintype "passive"))
      (node (ref "R53") (pin "1") (pinfunction "1_1") (pintype "passive"))
    )
    (net (code "123") (name "/PD24") (class "Default")
      (node (ref "J33") (pin "33") (pinfunction "33_33") (pintype "passive"))
      (node (ref "R170") (pin "1") (pinfunction "1_1") (pintype "passive"))
    )
    (net (code "124") (name "/PD29") (class "Default")
      (node (ref "C77") (pin "1") (pinfunction "1_1") (pintype "passive"))
      (node (ref "J32") (pin "4") (pinfunction "4_4") (pintype "passive"))
      (node (ref "R72") (pin "1") (pinfunction "1_1") (pintype "passive"))
    )
    (net (code "125") (name "/PD29_IO") (class "Default")
      (node (ref "D26") (pin "1") (pinfunction "C1_1") (pintype "passive"))
      (node (ref "J29") (pin "8") (pinfunction "8_8") (pintype "passive"))
      (node (ref "R149") (pin "1") (pinfunction "1_1") (pintype "passive"))
      (node (ref "R80") (pin "2") (pinfunction "2_2") (pintype "passive"))
    )
    (net (code "126") (name "/PD30") (class "Default")
      (node (ref "C56") (pin "2") (pinfunction "2_2") (pintype "passive"))
      (node (ref "J30") (pin "25") (pinfunction "25_25") (pintype "passive"))
      (node (ref "R48") (pin "1") (pinfunction "1_1") (pintype "passive"))
    )
    (net (code "127") (name "/PE0") (class "Default")
      (node (ref "J30") (pin "2") (pinfunction "2_2") (pintype "passive"))
      (node (ref "R84") (pin "1") (pinfunction "1_1") (pintype "passive"))
    )
    (net (code "128") (name "/PE1") (class "Default")
      (node (ref "D7") (pin "5") (pinfunction "5_cathode_5") (pintype "passive"))
      (node (ref "J3") (pin "7") (pinfunction "7_7") (pintype "passive"))
      (node (ref "J30") (pin "1") (pinfunction "1_1") (pintype "passive"))
    )
    (net (code "129") (name "/PE2") (class "Default")
      (node (ref "J30") (pin "7") (pinfunction "7_7") (pintype "passive"))
      (node (ref "R87") (pin "2") (pinfunction "2_2") (pintype "passive"))
    )
    (net (code "130") (name "/PE3") (class "Default")
      (node (ref "J30") (pin "8") (pinfunction "8_8") (pintype "passive"))
      (node (ref "R95") (pin "1") (pinfunction "1_1") (pintype "passive"))
    )
    (net (code "131") (name "/PE4") (class "Default")
      (node (ref "C57") (pin "2") (pinfunction "2_2") (pintype "passive"))
      (node (ref "J30") (pin "26") (pinfunction "26_26") (pintype "passive"))
      (node (ref "R49") (pin "1") (pinfunction "1_1") (pintype "passive"))
    )
    (net (code "132") (name "/PE5") (class "Default")
      (node (ref "J33") (pin "11") (pinfunction "11_11") (pintype "passive"))
      (node (ref "R94") (pin "1") (pinfunction "1_1") (pintype "passive"))
    )
    (net (code "133") (name "/PUL-") (class "Default")
      (node (ref "J8") (pin "4") (pinfunction "4_4") (pintype "passive"))
      (node (ref "Q1") (pin "3") (pinfunction "output(collector)_3") (pintype "passive"))
    )
    (net (code "134") (name "/QCS") (class "Default")
      (node (ref "J30") (pin "34") (pinfunction "34_34") (pintype "passive"))
      (node (ref "R101") (pin "1") (pinfunction "1_1") (pintype "passive"))
      (node (ref "U7") (pin "1") (pinfunction "~{CS}_1") (pintype "input"))
    )
    (net (code "135") (name "/QIO0") (class "Default")
      (node (ref "J30") (pin "31") (pinfunction "31_31") (pintype "passive"))
      (node (ref "U7") (pin "5") (pinfunction "SI/SIO0_5") (pintype "bidirectional"))
    )
    (net (code "136") (name "/QIO1") (class "Default")
      (node (ref "J30") (pin "33") (pinfunction "33_33") (pintype "passive"))
      (node (ref "U7") (pin "2") (pinfunction "SO/SIO1_2") (pintype "output"))
    )
    (net (code "137") (name "/QIO2") (class "Default")
      (node (ref "C28") (pin "2") (pinfunction "2_2") (pintype "passive"))
      (node (ref "J30") (pin "32") (pinfunction "32_32") (pintype "passive"))
      (node (ref "R26") (pin "1") (pinfunction "1_1") (pintype "passive"))
      (node (ref "U7") (pin "3") (pinfunction "~{WP}_3") (pintype "input"))
    )
    (net (code "138") (name "/QIO3") (class "Default")
      (node (ref "J30") (pin "30") (pinfunction "30_30") (pintype "passive"))
      (node (ref "R25") (pin "1") (pinfunction "1_1") (pintype "passive"))
      (node (ref "U7") (pin "7") (pinfunction "~{HOLD}_7") (pintype "input"))
    )
    (net (code "139") (name "/QSCK") (class "Default")
      (node (ref "J30") (pin "29") (pinfunction "29_29") (pintype "passive"))
      (node (ref "U7") (pin "6") (pinfunction "SCLK_6") (pintype "input"))
    )
    (net (code "140") (name "/RN1SJ1") (class "Default")
      (node (ref "RN1") (pin "2") (pinfunction "2_2") (pintype "passive"))
      (node (ref "S1") (pin "2B") (pinfunction "NO2_2B") (pintype "passive"))
    )
    (net (code "141") (name "/RN1SJ2") (class "Default")
      (node (ref "RN1") (pin "1") (pinfunction "1_1") (pintype "passive"))
      (node (ref "S1") (pin "3B") (pinfunction "NO3_3B") (pintype "passive"))
    )
    (net (code "142") (name "/RTS") (class "Default")
      (node (ref "RN1") (pin "3") (pinfunction "3_3") (pintype "passive"))
      (node (ref "U8") (pin "16") (pinfunction "~{RTS!/DIO6}_16") (pintype "bidirectional"))
    )
    (net (code "143") (name "/RTS0") (class "Default")
      (node (ref "J30") (pin "20") (pinfunction "20_20") (pintype "passive"))
      (node (ref "RN1") (pin "5") (pinfunction "5_5") (pintype "passive"))
    )
    (net (code "144") (name "/RTS1") (class "Default")
      (node (ref "J20") (pin "5") (pinfunction "5_5") (pintype "passive"))
      (node (ref "J33") (pin "28") (pinfunction "28_28") (pintype "passive"))
    )
    (net (code "145") (name "/RTS2") (class "Default")
      (node (ref "J21") (pin "5") (pinfunction "5_5") (pintype "passive"))
      (node (ref "J33") (pin "27") (pinfunction "27_27") (pintype "passive"))
    )
    (net (code "146") (name "/RTSJP1") (class "Default")
      (node (ref "J5") (pin "6") (pinfunction "S_6") (pintype "passive"))
      (node (ref "R169") (pin "1") (pinfunction "1_1") (pintype "passive"))
    )
    (net (code "147") (name "/RX") (class "Default")
      (node (ref "J49") (pin "3") (pinfunction "S_3") (pintype "passive"))
      (node (ref "S1") (pin "4B") (pinfunction "NO4_4B") (pintype "passive"))
    )
    (net (code "148") (name "/RXD0") (class "Default")
      (node (ref "J30") (pin "15") (pinfunction "15_15") (pintype "passive"))
      (node (ref "RN1") (pin "8") (pinfunction "8_8") (pintype "passive"))
    )
    (net (code "149") (name "/RXD1") (class "Default")
      (node (ref "J20") (pin "3") (pinfunction "3_3") (pintype "passive"))
      (node (ref "J33") (pin "20") (pinfunction "20_20") (pintype "passive"))
    )
    (net (code "150") (name "/RXD2") (class "Default")
      (node (ref "J21") (pin "3") (pinfunction "3_3") (pintype "passive"))
      (node (ref "J33") (pin "19") (pinfunction "19_19") (pintype "passive"))
    )
    (net (code "151") (name "/RXJP1") (class "Default")
      (node (ref "J5") (pin "3") (pinfunction "S_3") (pintype "passive"))
      (node (ref "R165") (pin "1") (pinfunction "1_1") (pintype "passive"))
    )
    (net (code "152") (name "/SCL0{slash}STAT1") (class "Default")
      (node (ref "D7") (pin "4") (pinfunction "3_cathode_4") (pintype "passive"))
      (node (ref "J3") (pin "9") (pinfunction "9_9") (pintype "passive"))
      (node (ref "J32") (pin "19") (pinfunction "19_19") (pintype "passive"))
    )
    (net (code "153") (name "/SCL2") (class "Default")
      (node (ref "D8") (pin "1") (pinfunction "1_cathode_1") (pintype "passive"))
      (node (ref "J3") (pin "3") (pinfunction "3_3") (pintype "passive"))
      (node (ref "J33") (pin "6") (pinfunction "6_6") (pintype "passive"))
      (node (ref "R22") (pin "1") (pinfunction "1_1") (pintype "passive"))
      (node (ref "R4") (pin "1") (pinfunction "1_1") (pintype "passive"))
      (node (ref "R42") (pin "1") (pinfunction "1_1") (pintype "passive"))
    )
    (net (code "154") (name "/SDA0{slash}STAT2") (class "Default")
      (node (ref "D7") (pin "3") (pinfunction "2_cathode_3") (pintype "passive"))
      (node (ref "J3") (pin "8") (pinfunction "8_8") (pintype "passive"))
      (node (ref "J32") (pin "20") (pinfunction "20_20") (pintype "passive"))
    )
    (net (code "155") (name "/SDA2") (class "Default")
      (node (ref "D8") (pin "5") (pinfunction "5_cathode_5") (pintype "passive"))
      (node (ref "J3") (pin "2") (pinfunction "2_2") (pintype "passive"))
      (node (ref "J33") (pin "5") (pinfunction "5_5") (pintype "passive"))
      (node (ref "R12") (pin "1") (pinfunction "1_1") (pintype "passive"))
      (node (ref "R24") (pin "1") (pinfunction "1_1") (pintype "passive"))
      (node (ref "R45") (pin "1") (pinfunction "1_1") (pintype "passive"))
    )
    (net (code "156") (name "/SPI0_MISO") (class "Default")
      (node (ref "J33") (pin "4") (pinfunction "4_4") (pintype "passive"))
      (node (ref "RN3") (pin "8") (pinfunction "8_8") (pintype "passive"))
    )
    (net (code "157") (name "/SPI0_MOSI") (class "Default")
      (node (ref "J33") (pin "2") (pinfunction "2_2") (pintype "passive"))
      (node (ref "RN3") (pin "6") (pinfunction "6_6") (pintype "passive"))
    )
    (net (code "158") (name "/SPI0_NPCS1") (class "Default")
      (node (ref "J33") (pin "3") (pinfunction "3_3") (pintype "passive"))
      (node (ref "RN3") (pin "7") (pinfunction "7_7") (pintype "passive"))
    )
    (net (code "159") (name "/SPI0_SPCK") (class "Default")
      (node (ref "J33") (pin "1") (pinfunction "1_1") (pintype "passive"))
      (node (ref "RN3") (pin "5") (pinfunction "5_5") (pintype "passive"))
    )
    (net (code "160") (name "/SPI1_MISO") (class "Default")
      (node (ref "J30") (pin "3") (pinfunction "3_3") (pintype "passive"))
      (node (ref "R19") (pin "1") (pinfunction "1_1") (pintype "passive"))
      (node (ref "R39") (pin "1") (pinfunction "1_1") (pintype "passive"))
      (node (ref "R55") (pin "1") (pinfunction "1_1") (pintype "passive"))
    )
    (net (code "161") (name "/SPI1_MOSI") (class "Default")
      (node (ref "J30") (pin "4") (pinfunction "4_4") (pintype "passive"))
      (node (ref "R21") (pin "1") (pinfunction "1_1") (pintype "passive"))
      (node (ref "R41") (pin "1") (pinfunction "1_1") (pintype "passive"))
      (node (ref "R59") (pin "1") (pinfunction "1_1") (pintype "passive"))
    )
    (net (code "162") (name "/SPI1_NPCS0") (class "Default")
      (node (ref "J31") (pin "19") (pinfunction "19_19") (pintype "passive"))
      (node (ref "R16") (pin "2") (pinfunction "2_2") (pintype "passive"))
    )
    (net (code "163") (name "/SPI1_NPCS1") (class "Default")
      (node (ref "J32") (pin "30") (pinfunction "30_30") (pintype "passive"))
      (node (ref "R52") (pin "2") (pinfunction "2_2") (pintype "passive"))
    )
    (net (code "164") (name "/SPI1_NPCS2") (class "Default")
      (node (ref "J32") (pin "16") (pinfunction "16_16") (pintype "passive"))
      (node (ref "R32") (pin "2") (pinfunction "2_2") (pintype "passive"))
    )
    (net (code "165") (name "/SPI1_SPCK") (class "Default")
      (node (ref "J31") (pin "34") (pinfunction "34_34") (pintype "passive"))
      (node (ref "R20") (pin "2") (pinfunction "2_2") (pintype "passive"))
      (node (ref "R40") (pin "2") (pinfunction "2_2") (pintype "passive"))
      (node (ref "R56") (pin "2") (pinfunction "2_2") (pintype "passive"))
    )
    (net (code "166") (name "/TX") (class "Default")
      (node (ref "J49") (pin "2") (pinfunction "S_2") (pintype "passive"))
      (node (ref "S1") (pin "1B") (pinfunction "NO1_1B") (pintype "passive"))
    )
    (net (code "167") (name "/TXD0") (class "Default")
      (node (ref "J30") (pin "16") (pinfunction "16_16") (pintype "passive"))
      (node (ref "RN1") (pin "7") (pinfunction "7_7") (pintype "passive"))
    )
    (net (code "168") (name "/TXD1") (class "Default")
      (node (ref "J20") (pin "2") (pinfunction "2_2") (pintype "passive"))
      (node (ref "J33") (pin "18") (pinfunction "18_18") (pintype "passive"))
    )
    (net (code "169") (name "/TXD2") (class "Default")
      (node (ref "J21") (pin "2") (pinfunction "2_2") (pintype "passive"))
      (node (ref "J33") (pin "17") (pinfunction "17_17") (pintype "passive"))
    )
    (net (code "170") (name "/TXJP1") (class "Default")
      (node (ref "J5") (pin "2") (pinfunction "S_2") (pintype "passive"))
      (node (ref "R163") (pin "1") (pinfunction "1_1") (pintype "passive"))
    )
    (net (code "171") (name "/URXD1") (class "Default")
      (node (ref "J32") (pin "33") (pinfunction "33_33") (pintype "passive"))
      (node (ref "R166") (pin "1") (pinfunction "1_1") (pintype "passive"))
    )
    (net (code "172") (name "/UTXD1") (class "Default")
      (node (ref "J32") (pin "34") (pinfunction "34_34") (pintype "passive"))
      (node (ref "R164") (pin "1") (pinfunction "1_1") (pintype "passive"))
    )
    (net (code "173") (name "/VBUS") (class "Default")
      (node (ref "J1") (pin "1") (pinfunction "VDD_1") (pintype "power_in"))
      (node (ref "U2") (pin "5") (pinfunction "VBUS_5") (pintype "power_in"))
    )
    (net (code "174") (name "/VCC") (class "Default")
      (node (ref "C34") (pin "2") (pinfunction "2_2") (pintype "passive"))
      (node (ref "L17") (pin "1") (pinfunction "1_1") (pintype "passive"))
      (node (ref "U8") (pin "1") (pinfunction "VCC_1") (pintype "power_in"))
    )
    (net (code "175") (name "/VDD_UART1") (class "Default")
      (node (ref "C68") (pin "1") (pinfunction "1_1") (pintype "passive"))
      (node (ref "J20") (pin "1") (pinfunction "1_1") (pintype "passive"))
      (node (ref "L2") (pin "1") (pinfunction "1_1") (pintype "passive"))
      (node (ref "L4") (pin "1") (pinfunction "1_1") (pintype "passive"))
      (node (ref "L6") (pin "1") (pinfunction "1_1") (pintype "passive"))
    )
    (net (code "176") (name "/VDD_UART2") (class "Default")
      (node (ref "C69") (pin "2") (pinfunction "2_2") (pintype "passive"))
      (node (ref "J21") (pin "1") (pinfunction "1_1") (pintype "passive"))
      (node (ref "L3") (pin "2") (pinfunction "2_2") (pintype "passive"))
      (node (ref "L5") (pin "2") (pinfunction "2_2") (pintype "passive"))
      (node (ref "L7") (pin "2") (pinfunction "2_2") (pintype "passive"))
    )
    (net (code "177") (name "GND") (class "Default")
      (node (ref "C1") (pin "1") (pinfunction "1_1") (pintype "passive"))
      (node (ref "C155") (pin "1") (pinfunction "1_1") (pintype "passive"))
      (node (ref "C190") (pin "1") (pinfunction "1_1") (pintype "passive"))
      (node (ref "C2") (pin "1") (pinfunction "1_1") (pintype "passive"))
      (node (ref "C28") (pin "1") (pinfunction "1_1") (pintype "passive"))
      (node (ref "C3") (pin "1") (pinfunction "1_1") (pintype "passive"))
      (node (ref "C33") (pin "1") (pinfunction "1_1") (pintype "passive"))
      (node (ref "C34") (pin "1") (pinfunction "1_1") (pintype "passive"))
      (node (ref "C35") (pin "1") (pinfunction "1_1") (pintype "passive"))
      (node (ref "C4") (pin "1") (pinfunction "1_1") (pintype "passive"))
      (node (ref "C56") (pin "1") (pinfunction "1_1") (pintype "passive"))
      (node (ref "C57") (pin "1") (pinfunction "1_1") (pintype "passive"))
      (node (ref "C58") (pin "1") (pinfunction "1_1") (pintype "passive"))
      (node (ref "C59") (pin "1") (pinfunction "1_1") (pintype "passive"))
      (node (ref "C61") (pin "1") (pinfunction "1_1") (pintype "passive"))
      (node (ref "C63") (pin "1") (pinfunction "1_1") (pintype "passive"))
      (node (ref "C68") (pin "2") (pinfunction "2_2") (pintype "passive"))
      (node (ref "C69") (pin "1") (pinfunction "1_1") (pintype "passive"))
      (node (ref "C70") (pin "2") (pinfunction "2_2") (pintype "passive"))
      (node (ref "C71") (pin "2") (pinfunction "2_2") (pintype "passive"))
      (node (ref "C72") (pin "2") (pinfunction "2_2") (pintype "passive"))
      (node (ref "C73") (pin "2") (pinfunction "2_2") (pintype "passive"))
      (node (ref "C74") (pin "2") (pinfunction "2_2") (pintype "passive"))
      (node (ref "C75") (pin "2") (pinfunction "2_2") (pintype "passive"))
      (node (ref "C76") (pin "2") (pinfunction "2_2") (pintype "passive"))
      (node (ref "C77") (pin "2") (pinfunction "2_2") (pintype "passive"))
      (node (ref "C78") (pin "1") (pinfunction "1_1") (pintype "passive"))
      (node (ref "C86") (pin "1") (pinfunction "1_1") (pintype "passive"))
      (node (ref "D10") (pin "2") (pinfunction "common_anode_2") (pintype "passive"))
      (node (ref "D11") (pin "4") (pinfunction "3_cathode_4") (pintype "passive"))
      (node (ref "D12") (pin "2") (pinfunction "common_anode_2") (pintype "passive"))
      (node (ref "D13") (pin "2") (pinfunction "common_anode_2") (pintype "passive"))
      (node (ref "D14") (pin "4") (pinfunction "3_cathode_4") (pintype "passive"))
      (node (ref "D15") (pin "1") (pinfunction "1_1") (pintype "passive"))
      (node (ref "D16") (pin "1") (pinfunction "1_1") (pintype "passive"))
      (node (ref "D17") (pin "1") (pinfunction "1_1") (pintype "passive"))
      (node (ref "D18") (pin "1") (pinfunction "1_1") (pintype "passive"))
      (node (ref "D19") (pin "1") (pinfunction "1_1") (pintype "passive"))
      (node (ref "D2") (pin "2") (pinfunction "2_2") (pintype "passive"))
      (node (ref "D20") (pin "1") (pinfunction "1_1") (pintype "passive"))
      (node (ref "D21") (pin "1") (pinfunction "1_1") (pintype "passive"))
      (node (ref "D22") (pin "1") (pinfunction "1_1") (pintype "passive"))
      (node (ref "D23") (pin "3") (pinfunction "CA_3") (pintype "passive"))
      (node (ref "D24") (pin "3") (pinfunction "CA_3") (pintype "passive"))
      (node (ref "D25") (pin "3") (pinfunction "CA_3") (pintype "passive"))
      (node (ref "D26") (pin "3") (pinfunction "CA_3") (pintype "passive"))
      (node (ref "D3") (pin "1") (pinfunction "1_1") (pintype "passive"))
      (node (ref "D31") (pin "1") (pinfunction "1_1") (pintype "passive"))
      (node (ref "D33") (pin "1") (pinfunction "1_1") (pintype "passive"))
      (node (ref "D35") (pin "1") (pinfunction "1_1") (pintype "passive"))
      (node (ref "D37") (pin "1") (pinfunction "1_1") (pintype "passive"))
      (node (ref "D4") (pin "1") (pinfunction "1_1") (pintype "passive"))
      (node (ref "D42") (pin "2") (pinfunction "common_anode_2") (pintype "passive"))
      (node (ref "D43") (pin "2") (pinfunction "common_anode_2") (pintype "passive"))
      (node (ref "D44") (pin "4") (pinfunction "3_cathode_4") (pintype "passive"))
      (node (ref "D46") (pin "2") (pinfunction "2_2") (pintype "passive"))
      (node (ref "D48") (pin "2") (pinfunction "2_2") (pintype "passive"))
      (node (ref "D5") (pin "1") (pinfunction "1_1") (pintype "passive"))
      (node (ref "D50") (pin "2") (pinfunction "2_2") (pintype "passive"))
      (node (ref "D6") (pin "1") (pinfunction "1_1") (pintype "passive"))
      (node (ref "D7") (pin "2") (pinfunction "common_anode_2") (pintype "passive"))
      (node (ref "D8") (pin "2") (pinfunction "common_anode_2") (pintype "passive"))
      (node (ref "D9") (pin "2") (pinfunction "common_anode_2") (pintype "passive"))
      (node (ref "GND1") (pin "1") (pinfunction "VSS_1") (pintype "passive"))
      (node (ref "GND2") (pin "1") (pinfunction "VSS_1") (pintype "passive"))
      (node (ref "GND3") (pin "1") (pinfunction "VSS_1") (pintype "passive"))
      (node (ref "GND4") (pin "1") (pinfunction "VSS_1") (pintype "passive"))
      (node (ref "J1") (pin "5") (pinfunction "GND_5") (pintype "power_in"))
      (node (ref "J10") (pin "2") (pinfunction "2_2") (pintype "passive"))
      (node (ref "J11") (pin "2") (pinfunction "2_2") (pintype "passive"))
      (node (ref "J15") (pin "4") (pinfunction "4_4") (pintype "passive"))
      (node (ref "J15") (pin "5") (pinfunction "5_5") (pintype "passive"))
      (node (ref "J15") (pin "M1") (pinfunction "M1_M1") (pintype "passive"))
      (node (ref "J15") (pin "M2") (pinfunction "M2_M2") (pintype "passive"))
      (node (ref "J16") (pin "4") (pinfunction "4_4") (pintype "passive"))
      (node (ref "J16") (pin "5") (pinfunction "5_5") (pintype "passive"))
      (node (ref "J16") (pin "M1") (pinfunction "M1_M1") (pintype "passive"))
      (node (ref "J16") (pin "M2") (pinfunction "M2_M2") (pintype "passive"))
      (node (ref "J17") (pin "4") (pinfunction "4_4") (pintype "passive"))
      (node (ref "J17") (pin "5") (pinfunction "5_5") (pintype "passive"))
      (node (ref "J17") (pin "M1") (pinfunction "M1_M1") (pintype "passive"))
      (node (ref "J17") (pin "M2") (pinfunction "M2_M2") (pintype "passive"))
      (node (ref "J18") (pin "4") (pinfunction "S_4") (pintype "passive"))
      (node (ref "J19") (pin "4") (pinfunction "S_4") (pintype "passive"))
      (node (ref "J20") (pin "8") (pinfunction "8_8") (pintype "passive"))
      (node (ref "J21") (pin "8") (pinfunction "8_8") (pintype "passive"))
      (node (ref "J28") (pin "6") (pinfunction "VSS_6") (pintype "power_in"))
      (node (ref "J28") (pin "P1") (pinfunction "SHIELD_P1") (pintype "passive"))
      (node (ref "J28") (pin "P2") (pinfunction "SHIELD_P2") (pintype "passive"))
      (node (ref "J28") (pin "P3") (pinfunction "SHIELD_P3") (pintype "passive"))
      (node (ref "J28") (pin "P4") (pinfunction "SHIELD_P4") (pintype "passive"))
      (node (ref "J28") (pin "SWB") (pinfunction "B_SWB") (pintype "bidirectional"))
      (node (ref "J3") (pin "10") (pinfunction "10_10") (pintype "passive"))
      (node (ref "J3") (pin "11") (pinfunction "11_11") (pintype "passive"))
      (node (ref "J3") (pin "M1") (pinfunction "M1_M1") (pintype "passive"))
      (node (ref "J3") (pin "M2") (pinfunction "M2_M2") (pintype "passive"))
      (node (ref "J30") (pin "21") (pinfunction "21_21") (pintype "passive"))
      (node (ref "J30") (pin "22") (pinfunction "22_22") (pintype "passive"))
      (node (ref "J30") (pin "23") (pinfunction "23_23") (pintype "passive"))
      (node (ref "J30") (pin "24") (pinfunction "24_24") (pintype "passive"))
      (node (ref "J30") (pin "9") (pinfunction "9_9") (pintype "passive"))
      (node (ref "J31") (pin "11") (pinfunction "11_11") (pintype "passive"))
      (node (ref "J31") (pin "12") (pinfunction "12_12") (pintype "passive"))
      (node (ref "J31") (pin "21") (pinfunction "21_21") (pintype "passive"))
      (node (ref "J31") (pin "22") (pinfunction "22_22") (pintype "passive"))
      (node (ref "J31") (pin "23") (pinfunction "23_23") (pintype "passive"))
      (node (ref "J31") (pin "24") (pinfunction "24_24") (pintype "passive"))
      (node (ref "J31") (pin "5") (pinfunction "5_5") (pintype "passive"))
      (node (ref "J31") (pin "6") (pinfunction "6_6") (pintype "passive"))
      (node (ref "J32") (pin "21") (pinfunction "21_21") (pintype "passive"))
      (node (ref "J32") (pin "22") (pinfunction "22_22") (pintype "passive"))
      (node (ref "J32") (pin "23") (pinfunction "23_23") (pintype "passive"))
      (node (ref "J32") (pin "24") (pinfunction "24_24") (pintype "passive"))
      (node (ref "J33") (pin "21") (pinfunction "21_21") (pintype "passive"))
      (node (ref "J33") (pin "22") (pinfunction "22_22") (pintype "passive"))
      (node (ref "J33") (pin "23") (pinfunction "23_23") (pintype "passive"))
      (node (ref "J33") (pin "24") (pinfunction "24_24") (pintype "passive"))
      (node (ref "J4") (pin "1") (pinfunction "1_1") (pintype "passive"))
      (node (ref "J49") (pin "4") (pinfunction "S_4") (pintype "passive"))
      (node (ref "J5") (pin "4") (pinfunction "S_4") (pintype "passive"))
      (node (ref "J51") (pin "2") (pinfunction "S_2") (pintype "passive"))
      (node (ref "J52") (pin "2") (pinfunction "S_2") (pintype "passive"))
      (node (ref "J6") (pin "2") (pinfunction "S_2") (pintype "passive"))
      (node (ref "J8") (pin "2") (pinfunction "2_2") (pintype "passive"))
      (node (ref "J9") (pin "2") (pinfunction "2_2") (pintype "passive"))
      (node (ref "LED10") (pin "C") (pinfunction "C_C") (pintype "passive"))
      (node (ref "LED13") (pin "C") (pinfunction "C_C") (pintype "passive"))
      (node (ref "LED14") (pin "C") (pinfunction "C_C") (pintype "passive"))
      (node (ref "LED15") (pin "C") (pinfunction "C_C") (pintype "passive"))
      (node (ref "LED6") (pin "C") (pinfunction "C_C") (pintype "passive"))
      (node (ref "Q1") (pin "2") (pinfunction "GND(emitter)_2") (pintype "passive"))
      (node (ref "Q2") (pin "2") (pinfunction "GND(emitter)_2") (pintype "passive"))
      (node (ref "Q3") (pin "2") (pinfunction "GND(emitter)_2") (pintype "passive"))
      (node (ref "Q4") (pin "2") (pinfunction "GND(emitter)_2") (pintype "passive"))
      (node (ref "Q5") (pin "2") (pinfunction "GND(emitter)_2") (pintype "passive"))
      (node (ref "Q6") (pin "2") (pinfunction "E_2") (pintype "passive"))
      (node (ref "Q7") (pin "2") (pinfunction "E_2") (pintype "passive"))
      (node (ref "Q8") (pin "2") (pinfunction "GND(emitter)_2") (pintype "passive"))
      (node (ref "Q9") (pin "2") (pinfunction "GND(emitter)_2") (pintype "passive"))
      (node (ref "R102") (pin "2") (pinfunction "2_2") (pintype "passive"))
      (node (ref "R143") (pin "2") (pinfunction "2_2") (pintype "passive"))
      (node (ref "R144") (pin "2") (pinfunction "2_2") (pintype "passive"))
      (node (ref "R148") (pin "2") (pinfunction "2_2") (pintype "passive"))
      (node (ref "R149") (pin "2") (pinfunction "2_2") (pintype "passive"))
      (node (ref "R150") (pin "2") (pinfunction "2_2") (pintype "passive"))
      (node (ref "R151") (pin "2") (pinfunction "2_2") (pintype "passive"))
      (node (ref "R152") (pin "2") (pinfunction "2_2") (pintype "passive"))
      (node (ref "R153") (pin "2") (pinfunction "2_2") (pintype "passive"))
      (node (ref "R154") (pin "2") (pinfunction "2_2") (pintype "passive"))
      (node (ref "R161") (pin "2") (pinfunction "2_2") (pintype "passive"))
      (node (ref "R162") (pin "1") (pinfunction "1_1") (pintype "passive"))
      (node (ref "R38") (pin "1") (pinfunction "1_1") (pintype "passive"))
      (node (ref "R63") (pin "2") (pinfunction "2_2") (pintype "passive"))
      (node (ref "R64") (pin "2") (pinfunction "2_2") (pintype "passive"))
      (node (ref "R81") (pin "2") (pinfunction "2_2") (pintype "passive"))
      (node (ref "R82") (pin "2") (pinfunction "2_2") (pintype "passive"))
      (node (ref "R85") (pin "2") (pinfunction "2_2") (pintype "passive"))
      (node (ref "R88") (pin "2") (pinfunction "2_2") (pintype "passive"))
      (node (ref "U1") (pin "11") (pinfunction "E_11") (pintype "passive"))
      (node (ref "U1") (pin "13") (pinfunction "E_13") (pintype "passive"))
      (node (ref "U1") (pin "15") (pinfunction "E_15") (pintype "passive"))
      (node (ref "U1") (pin "9") (pinfunction "E_9") (pintype "passive"))
      (node (ref "U2") (pin "2") (pinfunction "GND_2") (pintype "power_in"))
      (node (ref "U27") (pin "3") (pinfunction "GND_3") (pintype "passive"))
      (node (ref "U33") (pin "2") (pinfunction "GND_2") (pintype "power_in"))
      (node (ref "U7") (pin "4") (pinfunction "GND_4") (pintype "power_in"))
      (node (ref "U8") (pin "10") (pinfunction "GND_10") (pintype "power_in"))
    )
    (net (code "178") (name "Net-(D1-A)") (class "Default")
      (node (ref "D1") (pin "2") (pinfunction "A_2") (pintype "passive"))
      (node (ref "J2") (pin "1") (pinfunction "1_1") (pintype "passive"))
    )
    (net (code "179") (name "Net-(D15-Pad3)") (class "Default")
      (node (ref "D15") (pin "3") (pinfunction "3_3") (pintype "passive"))
      (node (ref "R57") (pin "1") (pinfunction "1_1") (pintype "passive"))
      (node (ref "R58") (pin "2") (pinfunction "2_2") (pintype "passive"))
      (node (ref "R63") (pin "1") (pinfunction "1_1") (pintype "passive"))
    )
    (net (code "180") (name "Net-(D16-Pad3)") (class "Default")
      (node (ref "D16") (pin "3") (pinfunction "3_3") (pintype "passive"))
      (node (ref "R144") (pin "1") (pinfunction "1_1") (pintype "passive"))
      (node (ref "R66") (pin "2") (pinfunction "2_2") (pintype "passive"))
      (node (ref "R74") (pin "1") (pinfunction "1_1") (pintype "passive"))
    )
    (net (code "181") (name "Net-(D17-Pad3)") (class "Default")
      (node (ref "D17") (pin "3") (pinfunction "3_3") (pintype "passive"))
      (node (ref "R143") (pin "1") (pinfunction "1_1") (pintype "passive"))
      (node (ref "R67") (pin "2") (pinfunction "2_2") (pintype "passive"))
      (node (ref "R75") (pin "1") (pinfunction "1_1") (pintype "passive"))
    )
    (net (code "182") (name "Net-(D18-Pad3)") (class "Default")
      (node (ref "D18") (pin "3") (pinfunction "3_3") (pintype "passive"))
      (node (ref "R102") (pin "1") (pinfunction "1_1") (pintype "passive"))
      (node (ref "R68") (pin "2") (pinfunction "2_2") (pintype "passive"))
      (node (ref "R76") (pin "1") (pinfunction "1_1") (pintype "passive"))
    )
    (net (code "183") (name "Net-(D19-Pad3)") (class "Default")
      (node (ref "D19") (pin "3") (pinfunction "3_3") (pintype "passive"))
      (node (ref "R69") (pin "2") (pinfunction "2_2") (pintype "passive"))
      (node (ref "R77") (pin "1") (pinfunction "1_1") (pintype "passive"))
      (node (ref "R88") (pin "1") (pinfunction "1_1") (pintype "passive"))
    )
    (net (code "184") (name "Net-(D20-Pad3)") (class "Default")
      (node (ref "D20") (pin "3") (pinfunction "3_3") (pintype "passive"))
      (node (ref "R70") (pin "2") (pinfunction "2_2") (pintype "passive"))
      (node (ref "R78") (pin "1") (pinfunction "1_1") (pintype "passive"))
      (node (ref "R85") (pin "1") (pinfunction "1_1") (pintype "passive"))
    )
    (net (code "185") (name "Net-(D21-Pad3)") (class "Default")
      (node (ref "D21") (pin "3") (pinfunction "3_3") (pintype "passive"))
      (node (ref "R71") (pin "2") (pinfunction "2_2") (pintype "passive"))
      (node (ref "R79") (pin "1") (pinfunction "1_1") (pintype "passive"))
      (node (ref "R82") (pin "1") (pinfunction "1_1") (pintype "passive"))
    )
    (net (code "186") (name "Net-(D22-Pad3)") (class "Default")
      (node (ref "D22") (pin "3") (pinfunction "3_3") (pintype "passive"))
      (node (ref "R72") (pin "2") (pinfunction "2_2") (pintype "passive"))
      (node (ref "R80") (pin "1") (pinfunction "1_1") (pintype "passive"))
      (node (ref "R81") (pin "1") (pinfunction "1_1") (pintype "passive"))
    )
    (net (code "187") (name "Net-(D31-Pad3)") (class "Default")
      (node (ref "D31") (pin "3") (pinfunction "3_3") (pintype "passive"))
      (node (ref "R163") (pin "2") (pinfunction "2_2") (pintype "passive"))
      (node (ref "R164") (pin "2") (pinfunction "2_2") (pintype "passive"))
    )
    (net (code "188") (name "Net-(D33-Pad3)") (class "Default")
      (node (ref "D33") (pin "3") (pinfunction "3_3") (pintype "passive"))
      (node (ref "R165") (pin "2") (pinfunction "2_2") (pintype "passive"))
      (node (ref "R166") (pin "2") (pinfunction "2_2") (pintype "passive"))
    )
    (net (code "189") (name "Net-(D35-Pad3)") (class "Default")
      (node (ref "D35") (pin "3") (pinfunction "3_3") (pintype "passive"))
      (node (ref "R167") (pin "2") (pinfunction "2_2") (pintype "passive"))
      (node (ref "R168") (pin "2") (pinfunction "2_2") (pintype "passive"))
    )
    (net (code "190") (name "Net-(D37-Pad3)") (class "Default")
      (node (ref "D37") (pin "3") (pinfunction "3_3") (pintype "passive"))
      (node (ref "R169") (pin "2") (pinfunction "2_2") (pintype "passive"))
      (node (ref "R170") (pin "2") (pinfunction "2_2") (pintype "passive"))
    )
    (net (code "191") (name "Net-(J18B-S)") (class "Default")
      (node (ref "D5") (pin "3") (pinfunction "3_3") (pintype "passive"))
      (node (ref "J18") (pin "2") (pinfunction "S_2") (pintype "passive"))
      (node (ref "R157") (pin "1") (pinfunction "1_1") (pintype "passive"))
      (node (ref "R50") (pin "2") (pinfunction "2_2") (pintype "passive"))
    )
    (net (code "192") (name "Net-(J18C-S)") (class "Default")
      (node (ref "D6") (pin "3") (pinfunction "3_3") (pintype "passive"))
      (node (ref "J18") (pin "3") (pinfunction "S_3") (pintype "passive"))
      (node (ref "R158") (pin "2") (pinfunction "2_2") (pintype "passive"))
      (node (ref "R51") (pin "2") (pinfunction "2_2") (pintype "passive"))
    )
    (net (code "193") (name "Net-(J19B-S)") (class "Default")
      (node (ref "D4") (pin "3") (pinfunction "3_3") (pintype "passive"))
      (node (ref "J19") (pin "2") (pinfunction "S_2") (pintype "passive"))
      (node (ref "R161") (pin "1") (pinfunction "1_1") (pintype "passive"))
      (node (ref "R49") (pin "2") (pinfunction "2_2") (pintype "passive"))
    )
    (net (code "194") (name "Net-(J19C-S)") (class "Default")
      (node (ref "D3") (pin "3") (pinfunction "3_3") (pintype "passive"))
      (node (ref "J19") (pin "3") (pinfunction "S_3") (pintype "passive"))
      (node (ref "R162") (pin "2") (pinfunction "2_2") (pintype "passive"))
      (node (ref "R48") (pin "2") (pinfunction "2_2") (pintype "passive"))
    )
    (net (code "195") (name "Net-(J47B-S)") (class "Default")
      (node (ref "J47") (pin "2") (pinfunction "S_2") (pintype "passive"))
      (node (ref "Q7") (pin "3") (pinfunction "C_3") (pintype "passive"))
    )
    (net (code "196") (name "Net-(J48B-S)") (class "Default")
      (node (ref "J48") (pin "2") (pinfunction "S_2") (pintype "passive"))
      (node (ref "Q6") (pin "3") (pinfunction "C_3") (pintype "passive"))
    )
    (net (code "197") (name "Net-(LED1-PadA)") (class "Default")
      (node (ref "LED1") (pin "A") (pinfunction "A_A") (pintype "passive"))
      (node (ref "R5") (pin "1") (pinfunction "1_1") (pintype "passive"))
    )
    (net (code "198") (name "Net-(LED2-PadA)") (class "Default")
      (node (ref "LED2") (pin "A") (pinfunction "A_A") (pintype "passive"))
      (node (ref "R6") (pin "1") (pinfunction "1_1") (pintype "passive"))
    )
    (net (code "199") (name "Net-(LED3-PadA)") (class "Default")
      (node (ref "LED3") (pin "A") (pinfunction "A_A") (pintype "passive"))
      (node (ref "R8") (pin "1") (pinfunction "1_1") (pintype "passive"))
    )
    (net (code "200") (name "Net-(LED4-PadA)") (class "Default")
      (node (ref "LED4") (pin "A") (pinfunction "A_A") (pintype "passive"))
      (node (ref "R10") (pin "1") (pinfunction "1_1") (pintype "passive"))
    )
    (net (code "201") (name "Net-(LED6-PadA)") (class "Default")
      (node (ref "LED6") (pin "A") (pinfunction "A_A") (pintype "passive"))
      (node (ref "R9") (pin "1") (pinfunction "1_1") (pintype "passive"))
    )
    (net (code "202") (name "Net-(LED10-PadA)") (class "Default")
      (node (ref "LED10") (pin "A") (pinfunction "A_A") (pintype "passive"))
      (node (ref "R13") (pin "1") (pinfunction "1_1") (pintype "passive"))
    )
    (net (code "203") (name "Net-(LED13-PadA)") (class "Default")
      (node (ref "LED13") (pin "A") (pinfunction "A_A") (pintype "passive"))
      (node (ref "R28") (pin "2") (pinfunction "2_2") (pintype "passive"))
    )
    (net (code "204") (name "Net-(LED14-PadA)") (class "Default")
      (node (ref "LED14") (pin "A") (pinfunction "A_A") (pintype "passive"))
      (node (ref "R30") (pin "2") (pinfunction "2_2") (pintype "passive"))
    )
    (net (code "205") (name "Net-(LED15-PadA)") (class "Default")
      (node (ref "LED15") (pin "A") (pinfunction "A_A") (pintype "passive"))
      (node (ref "R83") (pin "2") (pinfunction "2_2") (pintype "passive"))
    )
    (net (code "206") (name "Net-(Q2-output(collector))") (class "Default")
      (node (ref "LED1") (pin "C") (pinfunction "C_C") (pintype "passive"))
      (node (ref "Q2") (pin "3") (pinfunction "output(collector)_3") (pintype "passive"))
    )
    (net (code "207") (name "Net-(Q3-output(collector))") (class "Default")
      (node (ref "LED2") (pin "C") (pinfunction "C_C") (pintype "passive"))
      (node (ref "Q3") (pin "3") (pinfunction "output(collector)_3") (pintype "passive"))
    )
    (net (code "208") (name "Net-(Q4-output(collector))") (class "Default")
      (node (ref "LED3") (pin "C") (pinfunction "C_C") (pintype "passive"))
      (node (ref "Q4") (pin "3") (pinfunction "output(collector)_3") (pintype "passive"))
    )
    (net (code "209") (name "Net-(Q5-output(collector))") (class "Default")
      (node (ref "LED4") (pin "C") (pinfunction "C_C") (pintype "passive"))
      (node (ref "Q5") (pin "3") (pinfunction "output(collector)_3") (pintype "passive"))
    )
    (net (code "210") (name "Net-(Q6-B)") (class "Default")
      (node (ref "Q6") (pin "1") (pinfunction "B_1") (pintype "passive"))
      (node (ref "R98") (pin "2") (pinfunction "2_2") (pintype "passive"))
    )
    (net (code "211") (name "Net-(Q7-B)") (class "Default")
      (node (ref "C190") (pin "2") (pinfunction "2_2") (pintype "passive"))
      (node (ref "Q7") (pin "1") (pinfunction "B_1") (pintype "passive"))
      (node (ref "R44") (pin "1") (pinfunction "1_1") (pintype "passive"))
    )
    (net (code "212") (name "Net-(U1A-1_Cathode)") (class "Default")
      (node (ref "R3") (pin "1") (pinfunction "1_1") (pintype "passive"))
      (node (ref "U1") (pin "2") (pinfunction "1_Cathode_2") (pintype "passive"))
    )
    (net (code "213") (name "Net-(U1B-2_Anode)") (class "Default")
      (node (ref "R11") (pin "1") (pinfunction "1_1") (pintype "passive"))
      (node (ref "U1") (pin "3") (pinfunction "2_Anode_3") (pintype "passive"))
    )
    (net (code "214") (name "Net-(U1C-3_Anode)") (class "Default")
      (node (ref "R35") (pin "1") (pinfunction "1_1") (pintype "passive"))
      (node (ref "U1") (pin "5") (pinfunction "3_Anode_5") (pintype "passive"))
    )
    (net (code "215") (name "Net-(U1D-4_Anode)") (class "Default")
      (node (ref "R36") (pin "1") (pinfunction "1_1") (pintype "passive"))
      (node (ref "U1") (pin "7") (pinfunction "4_Anode_7") (pintype "passive"))
    )
    (net (code "216") (name "VDD_3.3V") (class "Default")
      (node (ref "C155") (pin "2") (pinfunction "2_2") (pintype "passive"))
      (node (ref "C2") (pin "2") (pinfunction "2_2") (pintype "passive"))
      (node (ref "C35") (pin "2") (pinfunction "2_2") (pintype "passive"))
      (node (ref "C78") (pin "2") (pinfunction "2_2") (pintype "passive"))
      (node (ref "C86") (pin "2") (pinfunction "2_2") (pintype "passive"))
      (node (ref "D15") (pin "2") (pinfunction "2_2") (pintype "passive"))
      (node (ref "D16") (pin "2") (pinfunction "2_2") (pintype "passive"))
      (node (ref "D17") (pin "2") (pinfunction "2_2") (pintype "passive"))
      (node (ref "D18") (pin "2") (pinfunction "2_2") (pintype "passive"))
      (node (ref "D19") (pin "2") (pinfunction "2_2") (pintype "passive"))
      (node (ref "D20") (pin "2") (pinfunction "2_2") (pintype "passive"))
      (node (ref "D21") (pin "2") (pinfunction "2_2") (pintype "passive"))
      (node (ref "D22") (pin "2") (pinfunction "2_2") (pintype "passive"))
      (node (ref "D3") (pin "2") (pinfunction "2_2") (pintype "passive"))
      (node (ref "D31") (pin "2") (pinfunction "2_2") (pintype "passive"))
      (node (ref "D33") (pin "2") (pinfunction "2_2") (pintype "passive"))
      (node (ref "D35") (pin "2") (pinfunction "2_2") (pintype "passive"))
      (node (ref "D37") (pin "2") (pinfunction "2_2") (pintype "passive"))
      (node (ref "D4") (pin "2") (pinfunction "2_2") (pintype "passive"))
      (node (ref "D46") (pin "1") (pinfunction "1_1") (pintype "passive"))
      (node (ref "D48") (pin "1") (pinfunction "1_1") (pintype "passive"))
      (node (ref "D5") (pin "2") (pinfunction "2_2") (pintype "passive"))
      (node (ref "D50") (pin "1") (pinfunction "1_1") (pintype "passive"))
      (node (ref "D6") (pin "2") (pinfunction "2_2") (pintype "passive"))
      (node (ref "J10") (pin "3") (pinfunction "3_3") (pintype "passive"))
      (node (ref "J11") (pin "3") (pinfunction "3_3") (pintype "passive"))
      (node (ref "J15") (pin "14") (pinfunction "14_14") (pintype "passive"))
      (node (ref "J15") (pin "15") (pinfunction "15_15") (pintype "passive"))
      (node (ref "J16") (pin "14") (pinfunction "14_14") (pintype "passive"))
      (node (ref "J16") (pin "15") (pinfunction "15_15") (pintype "passive"))
      (node (ref "J17") (pin "14") (pinfunction "14_14") (pintype "passive"))
      (node (ref "J17") (pin "15") (pinfunction "15_15") (pintype "passive"))
      (node (ref "J28") (pin "4") (pinfunction "VDD_4") (pintype "power_in"))
      (node (ref "J3") (pin "14") (pinfunction "14_14") (pintype "passive"))
      (node (ref "J3") (pin "15") (pinfunction "15_15") (pintype "passive"))
      (node (ref "J31") (pin "10") (pinfunction "10_10") (pintype "passive"))
      (node (ref "J31") (pin "7") (pinfunction "7_7") (pintype "passive"))
      (node (ref "J31") (pin "8") (pinfunction "8_8") (pintype "passive"))
      (node (ref "J31") (pin "9") (pinfunction "9_9") (pintype "passive"))
      (node (ref "J49") (pin "1") (pinfunction "S_1") (pintype "passive"))
      (node (ref "J5") (pin "1") (pinfunction "S_1") (pintype "passive"))
      (node (ref "J51") (pin "1") (pinfunction "S_1") (pintype "passive"))
      (node (ref "L17") (pin "2") (pinfunction "2_2") (pintype "passive"))
      (node (ref "L4") (pin "2") (pinfunction "2_2") (pintype "passive"))
      (node (ref "L5") (pin "1") (pinfunction "1_1") (pintype "passive"))
      (node (ref "R1") (pin "2") (pinfunction "2_2") (pintype "passive"))
      (node (ref "R10") (pin "2") (pinfunction "2_2") (pintype "passive"))
      (node (ref "R101") (pin "2") (pinfunction "2_2") (pintype "passive"))
      (node (ref "R128") (pin "2") (pinfunction "2_2") (pintype "passive"))
      (node (ref "R157") (pin "2") (pinfunction "2_2") (pintype "passive"))
      (node (ref "R158") (pin "1") (pinfunction "1_1") (pintype "passive"))
      (node (ref "R2") (pin "2") (pinfunction "2_2") (pintype "passive"))
      (node (ref "R25") (pin "2") (pinfunction "2_2") (pintype "passive"))
      (node (ref "R26") (pin "2") (pinfunction "2_2") (pintype "passive"))
      (node (ref "R29") (pin "2") (pinfunction "2_2") (pintype "passive"))
      (node (ref "R34") (pin "2") (pinfunction "2_2") (pintype "passive"))
      (node (ref "R5") (pin "2") (pinfunction "2_2") (pintype "passive"))
      (node (ref "R6") (pin "2") (pinfunction "2_2") (pintype "passive"))
      (node (ref "R60") (pin "1") (pinfunction "1_1") (pintype "passive"))
      (node (ref "R61") (pin "1") (pinfunction "1_1") (pintype "passive"))
      (node (ref "R62") (pin "1") (pinfunction "1_1") (pintype "passive"))
      (node (ref "R65") (pin "1") (pinfunction "1_1") (pintype "passive"))
      (node (ref "R73") (pin "1") (pinfunction "1_1") (pintype "passive"))
      (node (ref "R8") (pin "2") (pinfunction "2_2") (pintype "passive"))
      (node (ref "R86") (pin "1") (pinfunction "1_1") (pintype "passive"))
      (node (ref "R9") (pin "2") (pinfunction "2_2") (pintype "passive"))
      (node (ref "U27") (pin "2") (pinfunction "OUT_2") (pintype "passive"))
      (node (ref "U7") (pin "8") (pinfunction "VCC_8") (pintype "power_in"))
    )
    (net (code "217") (name "VDD_5V") (class "Default")
      (node (ref "C33") (pin "2") (pinfunction "2_2") (pintype "passive"))
      (node (ref "C4") (pin "2") (pinfunction "2_2") (pintype "passive"))
      (node (ref "C61") (pin "2") (pinfunction "2_2") (pintype "passive"))
      (node (ref "C63") (pin "2") (pinfunction "2_2") (pintype "passive"))
      (node (ref "J10") (pin "1") (pinfunction "1_1") (pintype "passive"))
      (node (ref "J18") (pin "1") (pinfunction "S_1") (pintype "passive"))
      (node (ref "J19") (pin "1") (pinfunction "S_1") (pintype "passive"))
      (node (ref "J3") (pin "12") (pinfunction "12_12") (pintype "passive"))
      (node (ref "J3") (pin "13") (pinfunction "13_13") (pintype "passive"))
      (node (ref "J47") (pin "1") (pinfunction "S_1") (pintype "passive"))
      (node (ref "J48") (pin "1") (pinfunction "S_1") (pintype "passive"))
      (node (ref "J52") (pin "1") (pinfunction "S_1") (pintype "passive"))
      (node (ref "J8") (pin "1") (pinfunction "1_1") (pintype "passive"))
      (node (ref "J8") (pin "3") (pinfunction "3_3") (pintype "passive"))
      (node (ref "J8") (pin "5") (pinfunction "5_5") (pintype "passive"))
      (node (ref "J8") (pin "7") (pinfunction "7_7") (pintype "passive"))
      (node (ref "J9") (pin "1") (pinfunction "1_1") (pintype "passive"))
      (node (ref "L6") (pin "2") (pinfunction "2_2") (pintype "passive"))
      (node (ref "L7") (pin "1") (pinfunction "1_1") (pintype "passive"))
      (node (ref "R13") (pin "2") (pinfunction "2_2") (pintype "passive"))
      (node (ref "U33") (pin "3") (pinfunction "OUT_3") (pintype "output"))
    )
    (net (code "218") (name "VDD_SYS") (class "Default")
      (node (ref "C1") (pin "2") (pinfunction "2_2") (pintype "passive"))
      (node (ref "C3") (pin "2") (pinfunction "2_2") (pintype "passive"))
      (node (ref "D1") (pin "1") (pinfunction "C_1") (pintype "passive"))
      (node (ref "D2") (pin "1") (pinfunction "1_1") (pintype "passive"))
      (node (ref "J11") (pin "1") (pinfunction "1_1") (pintype "passive"))
      (node (ref "J6") (pin "1") (pinfunction "S_1") (pintype "passive"))
      (node (ref "J9") (pin "3") (pinfunction "3_3") (pintype "passive"))
      (node (ref "L2") (pin "2") (pinfunction "2_2") (pintype "passive"))
      (node (ref "L3") (pin "1") (pinfunction "1_1") (pintype "passive"))
      (node (ref "R11") (pin "2") (pinfunction "2_2") (pintype "passive"))
      (node (ref "R3") (pin "2") (pinfunction "2_2") (pintype "passive"))
      (node (ref "R35") (pin "2") (pinfunction "2_2") (pintype "passive"))
      (node (ref "R36") (pin "2") (pinfunction "2_2") (pintype "passive"))
      (node (ref "U27") (pin "1") (pinfunction "IN_1") (pintype "passive"))
      (node (ref "U33") (pin "1") (pinfunction "IN_1") (pintype "input"))
    )
    (net (code "219") (name "unconnected-(D11-common_anode-Pad2)") (class "Default")
      (node (ref "D11") (pin "2") (pinfunction "common_anode_2") (pintype "passive"))
    )
    (net (code "220") (name "unconnected-(D14-common_anode-Pad2)") (class "Default")
      (node (ref "D14") (pin "2") (pinfunction "common_anode_2") (pintype "passive"))
    )
    (net (code "221") (name "unconnected-(D44-common_anode-Pad2)") (class "Default")
      (node (ref "D44") (pin "2") (pinfunction "common_anode_2") (pintype "passive"))
    )
    (net (code "222") (name "unconnected-(J1-ID-Pad4)") (class "Default")
      (node (ref "J1") (pin "4") (pinfunction "ID_4") (pintype "passive"))
    )
    (net (code "223") (name "unconnected-(U8-AD2{slash}DIO2{slash}SPI_CLK-Pad18)") (class "Default")
      (node (ref "U8") (pin "18") (pinfunction "AD2/DIO2/SPI_CLK_18") (pintype "bidirectional"))
    )
    (net (code "224") (name "unconnected-(U8-AD3{slash}DIO3{slash}SPI_!SSEL!-Pad17)") (class "Default")
      (node (ref "U8") (pin "17") (pinfunction "AD3/DIO3/SPI_!SSEL!_17") (pintype "bidirectional"))
    )
    (net (code "225") (name "unconnected-(U8-DIO4{slash}SPI_MOSI-Pad11)") (class "Default")
      (node (ref "U8") (pin "11") (pinfunction "DIO4/SPI_MOSI_11") (pintype "bidirectional"))
    )
    (net (code "226") (name "unconnected-(U8-DIO12{slash}SPI_MISO-Pad4)") (class "Default")
      (node (ref "U8") (pin "4") (pinfunction "DIO12/SPI_MISO_4") (pintype "bidirectional"))
    )
    (net (code "227") (name "unconnected-(U8-ON{slash}!SLEEP!{slash}DIO9-Pad13)") (class "Default")
      (node (ref "U8") (pin "13") (pinfunction "ON/!SLEEP!/DIO9_13") (pintype "bidirectional"))
    )
    (net (code "228") (name "unconnected-(U8-PWM1{slash}DIO11{slash}I2C_SDA-Pad7)") (class "Default")
      (node (ref "U8") (pin "7") (pinfunction "PWM1/DIO11/I2C_SDA_7") (pintype "bidirectional"))
    )
  )
)
